# openevsetester.net
KiCad netlist of a schematic drawn in EAGLE
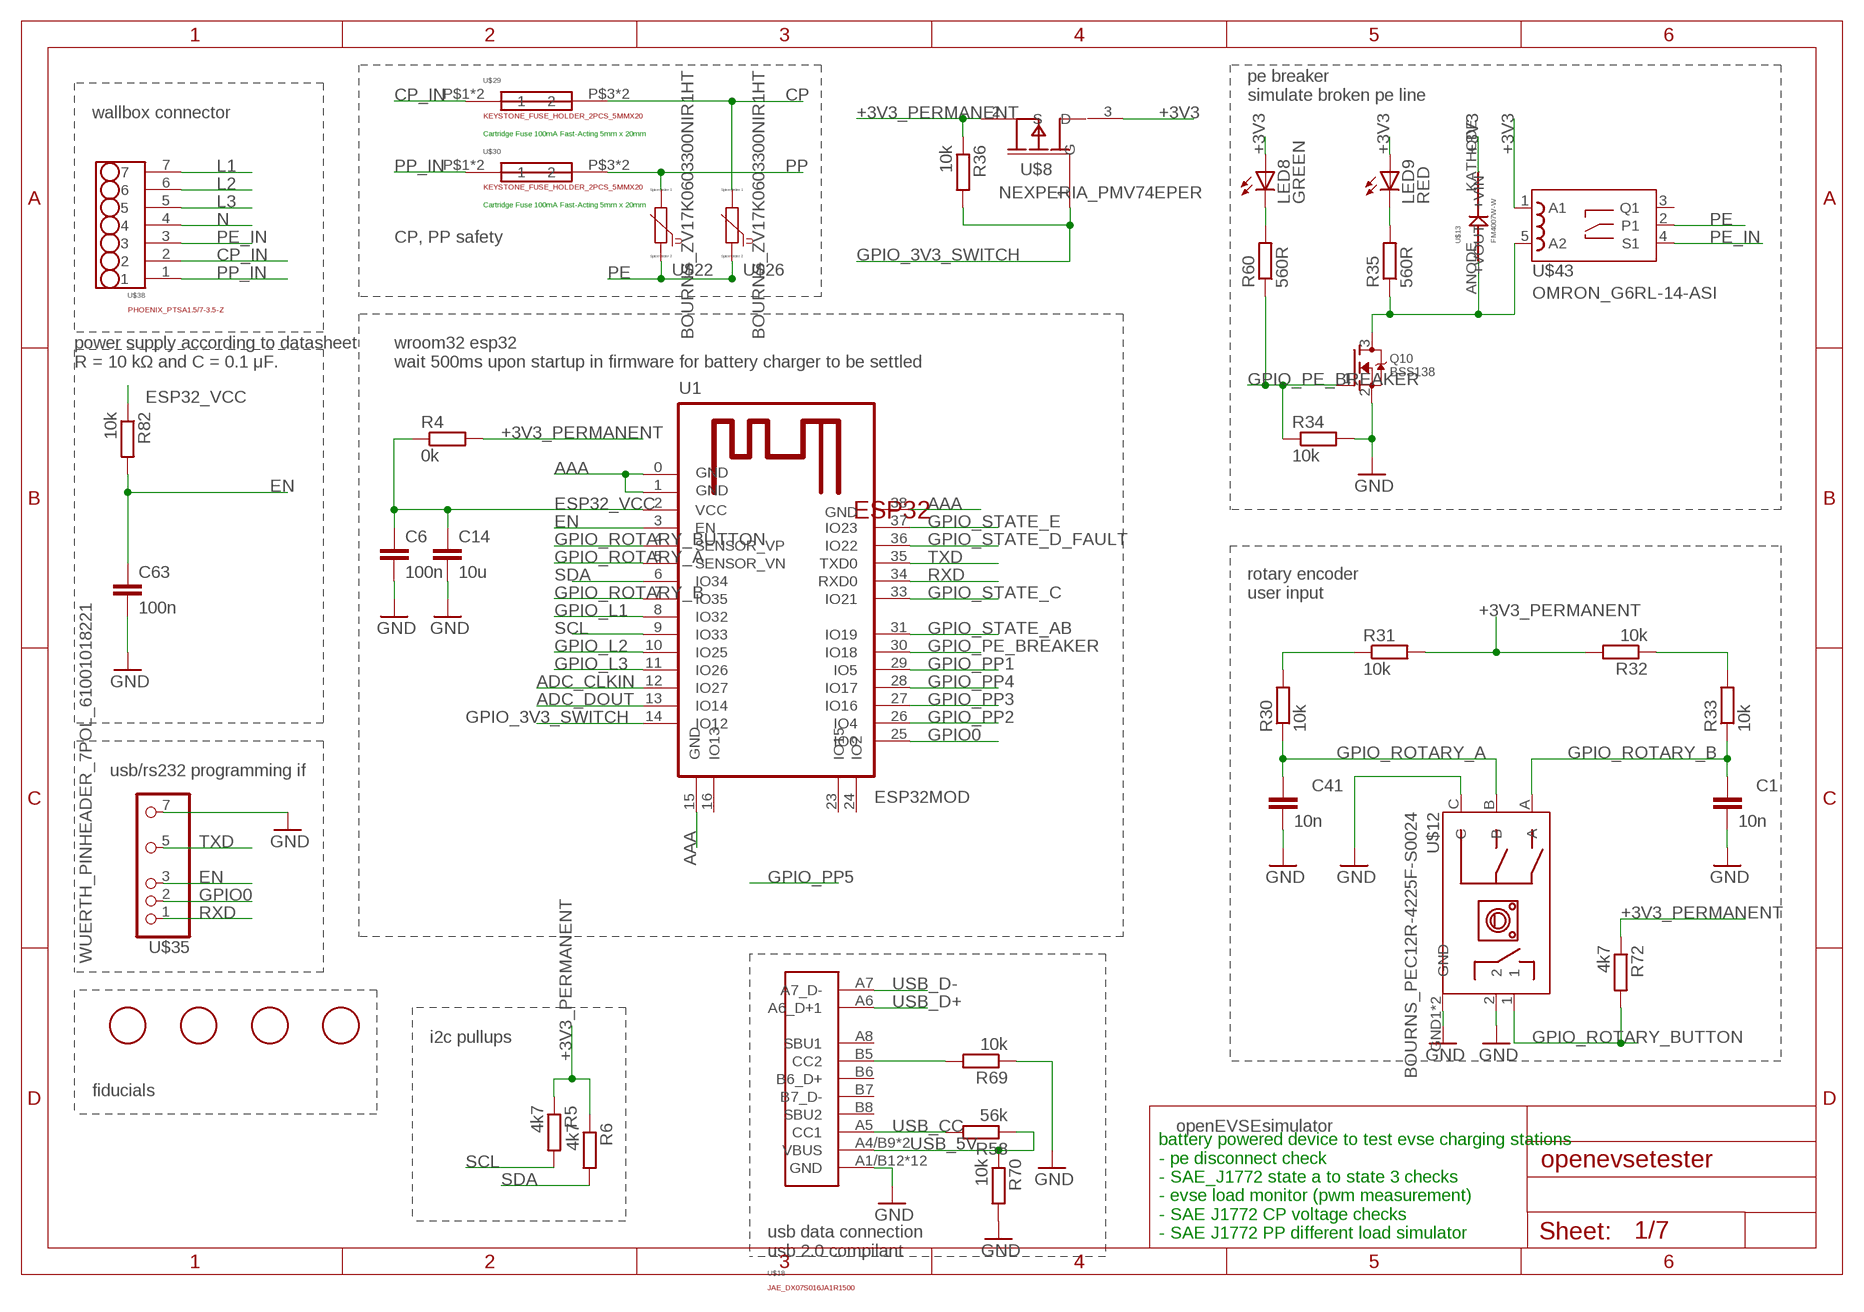
[diagram p0: schematic, sheet 1]
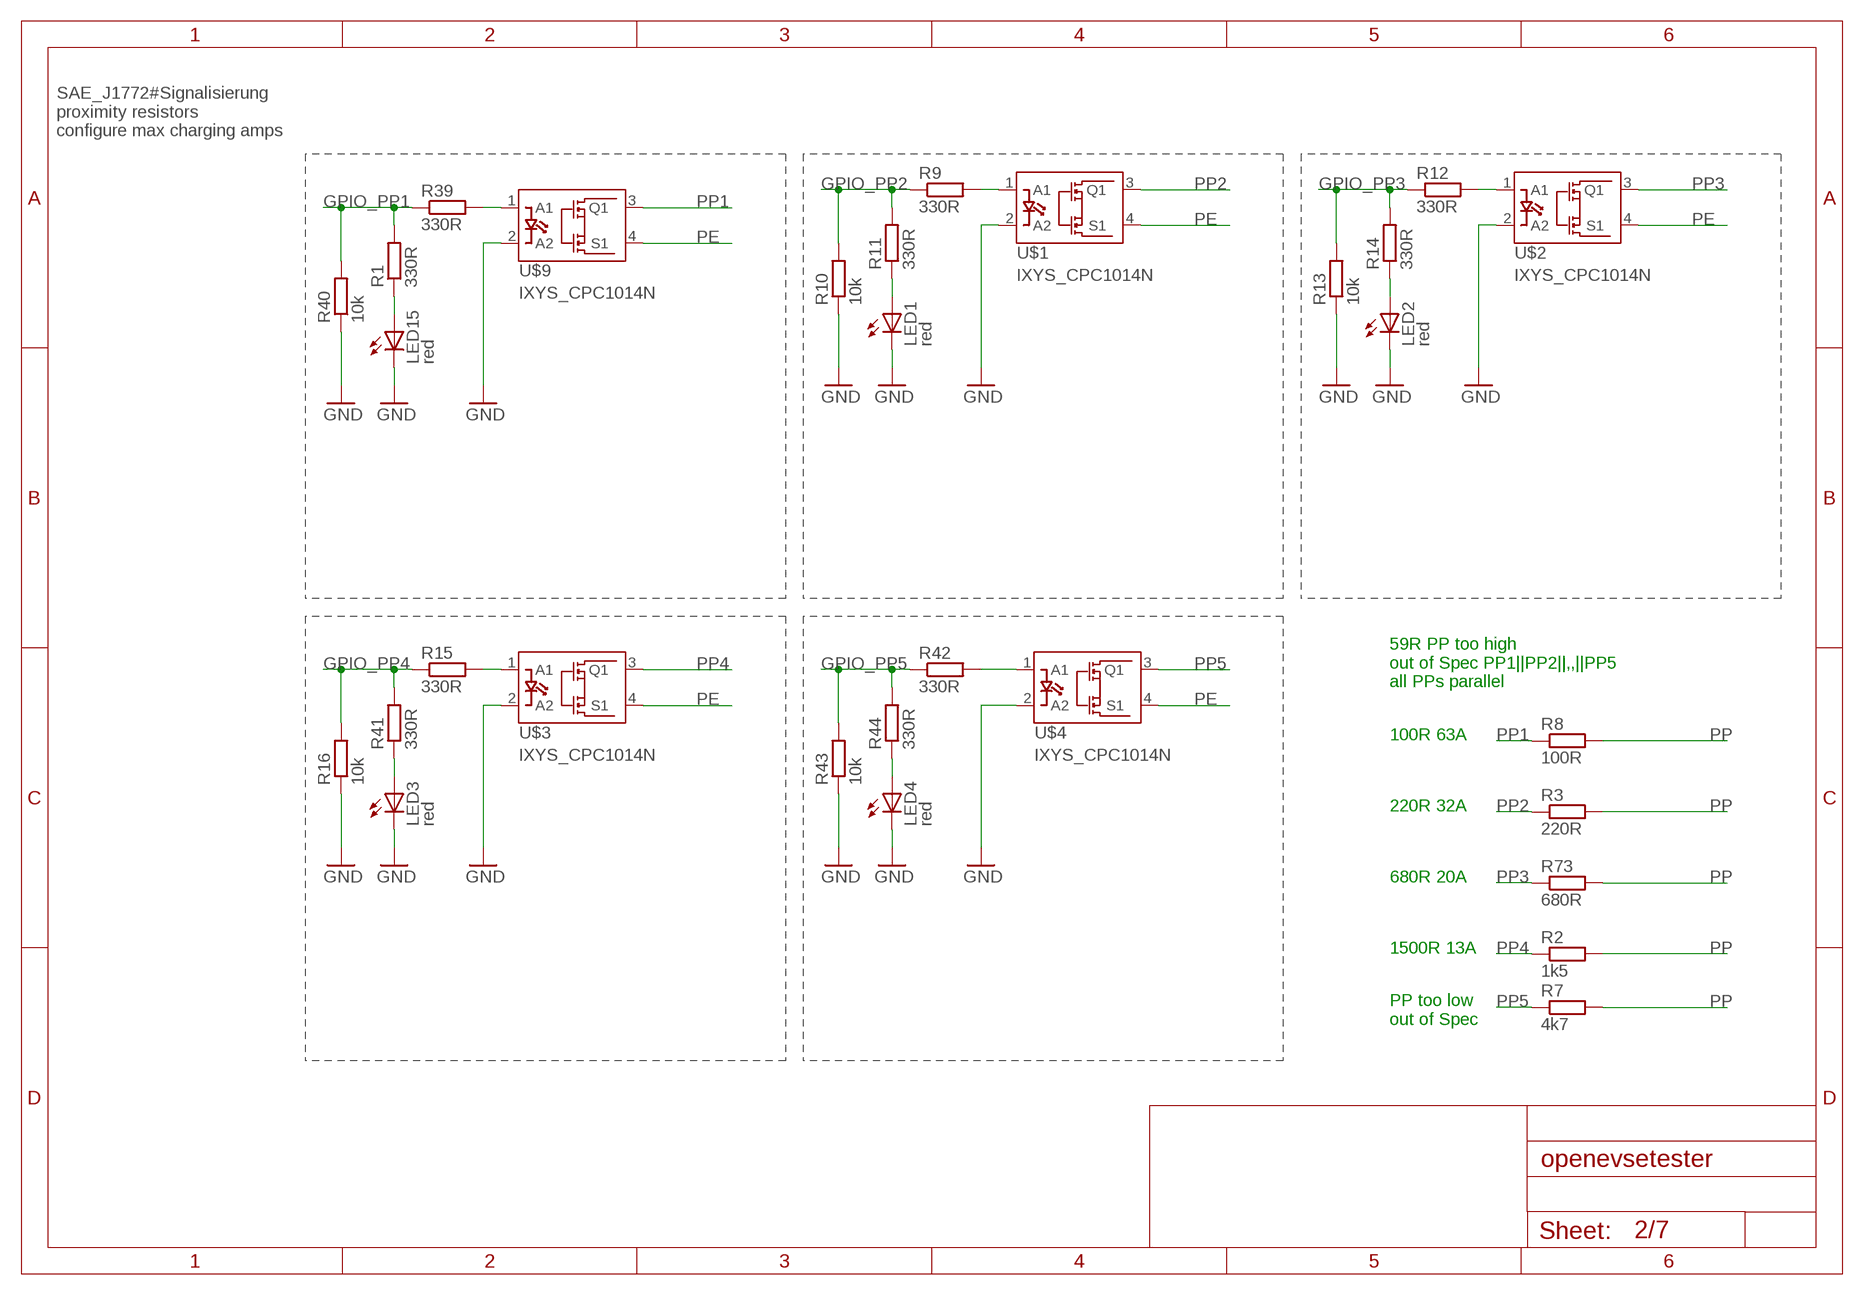
[diagram p1: schematic, sheet 2]
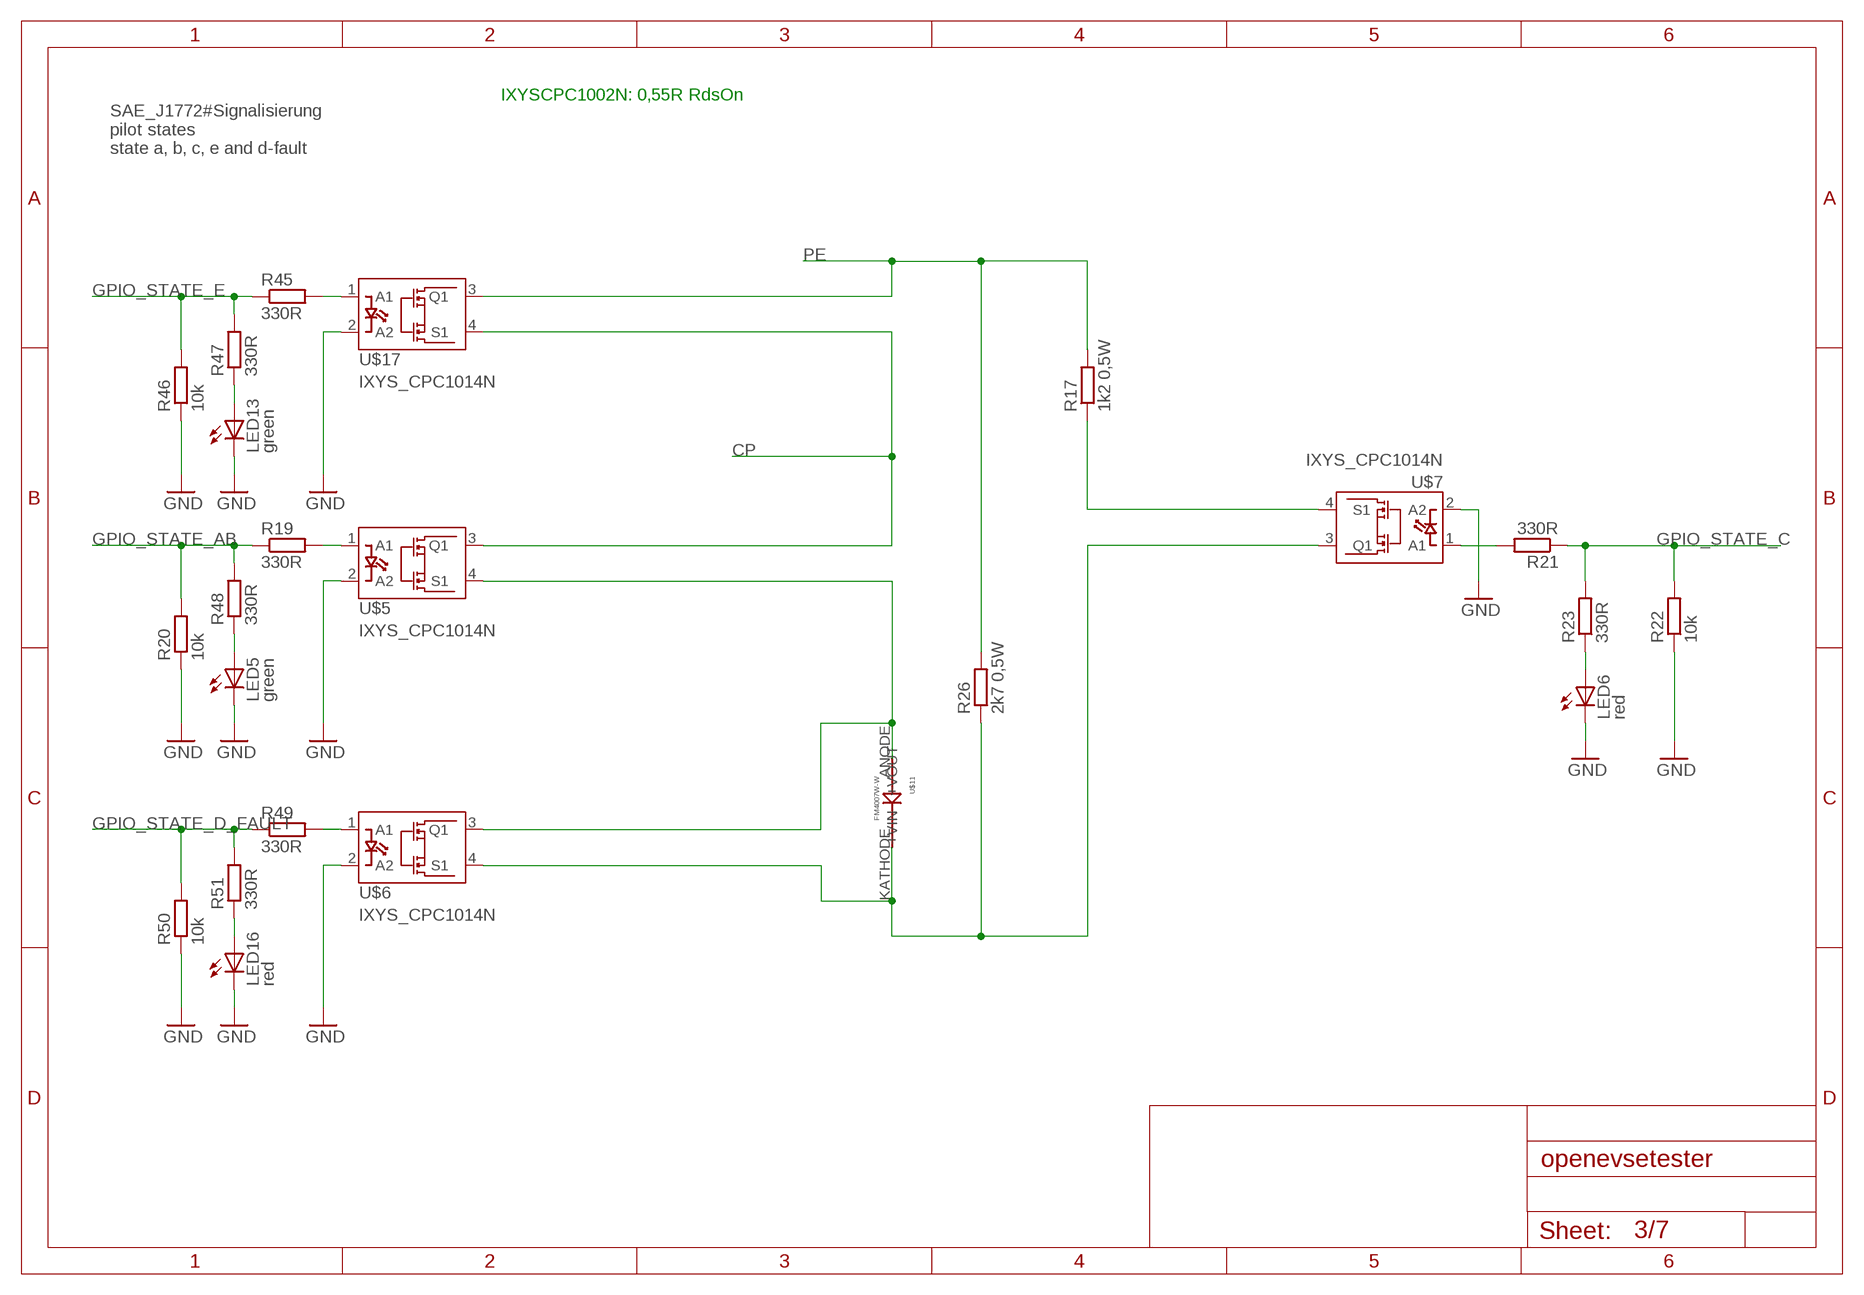
[diagram p2: schematic, sheet 3]
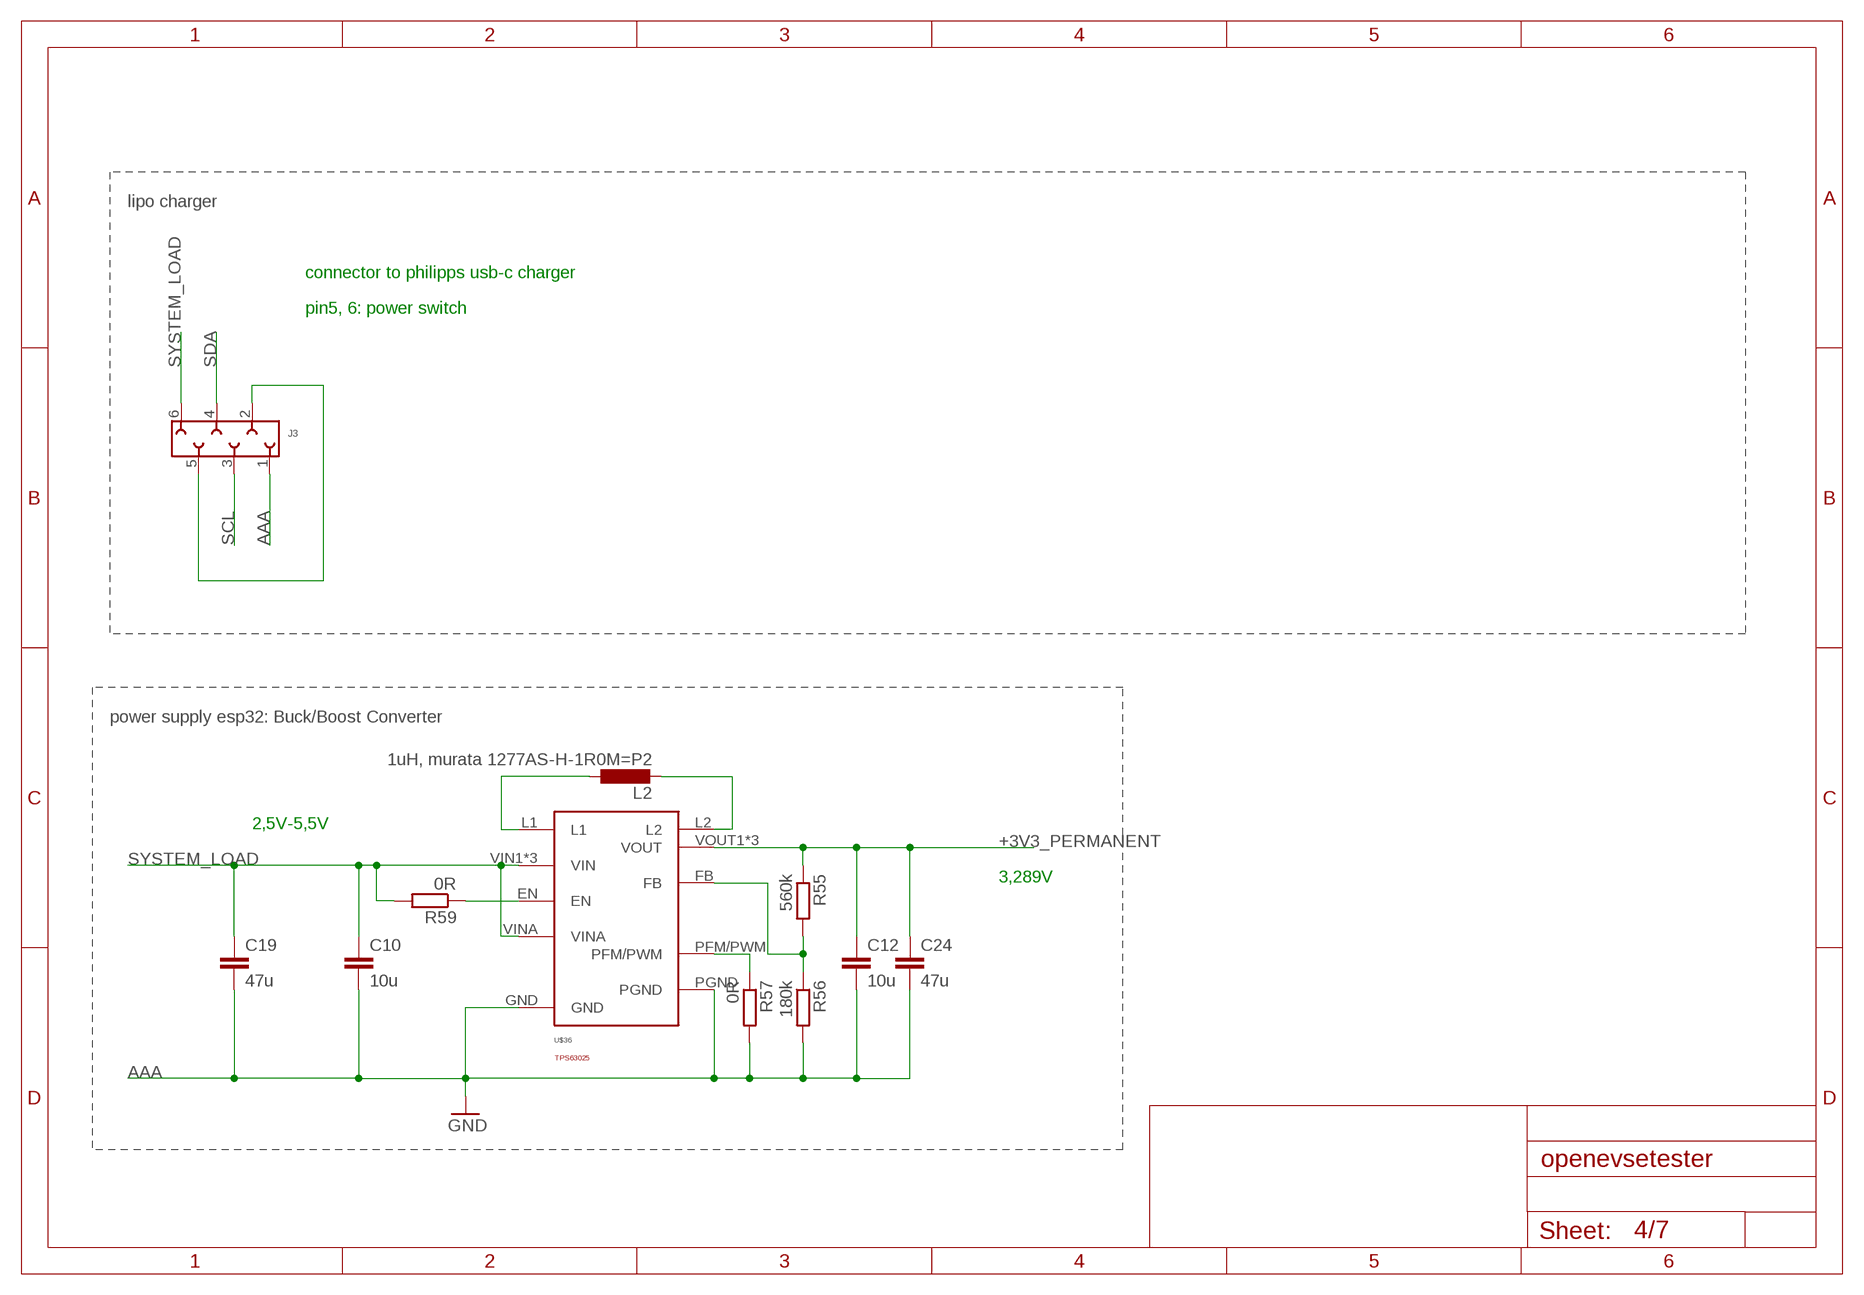
[diagram p3: schematic, sheet 4]
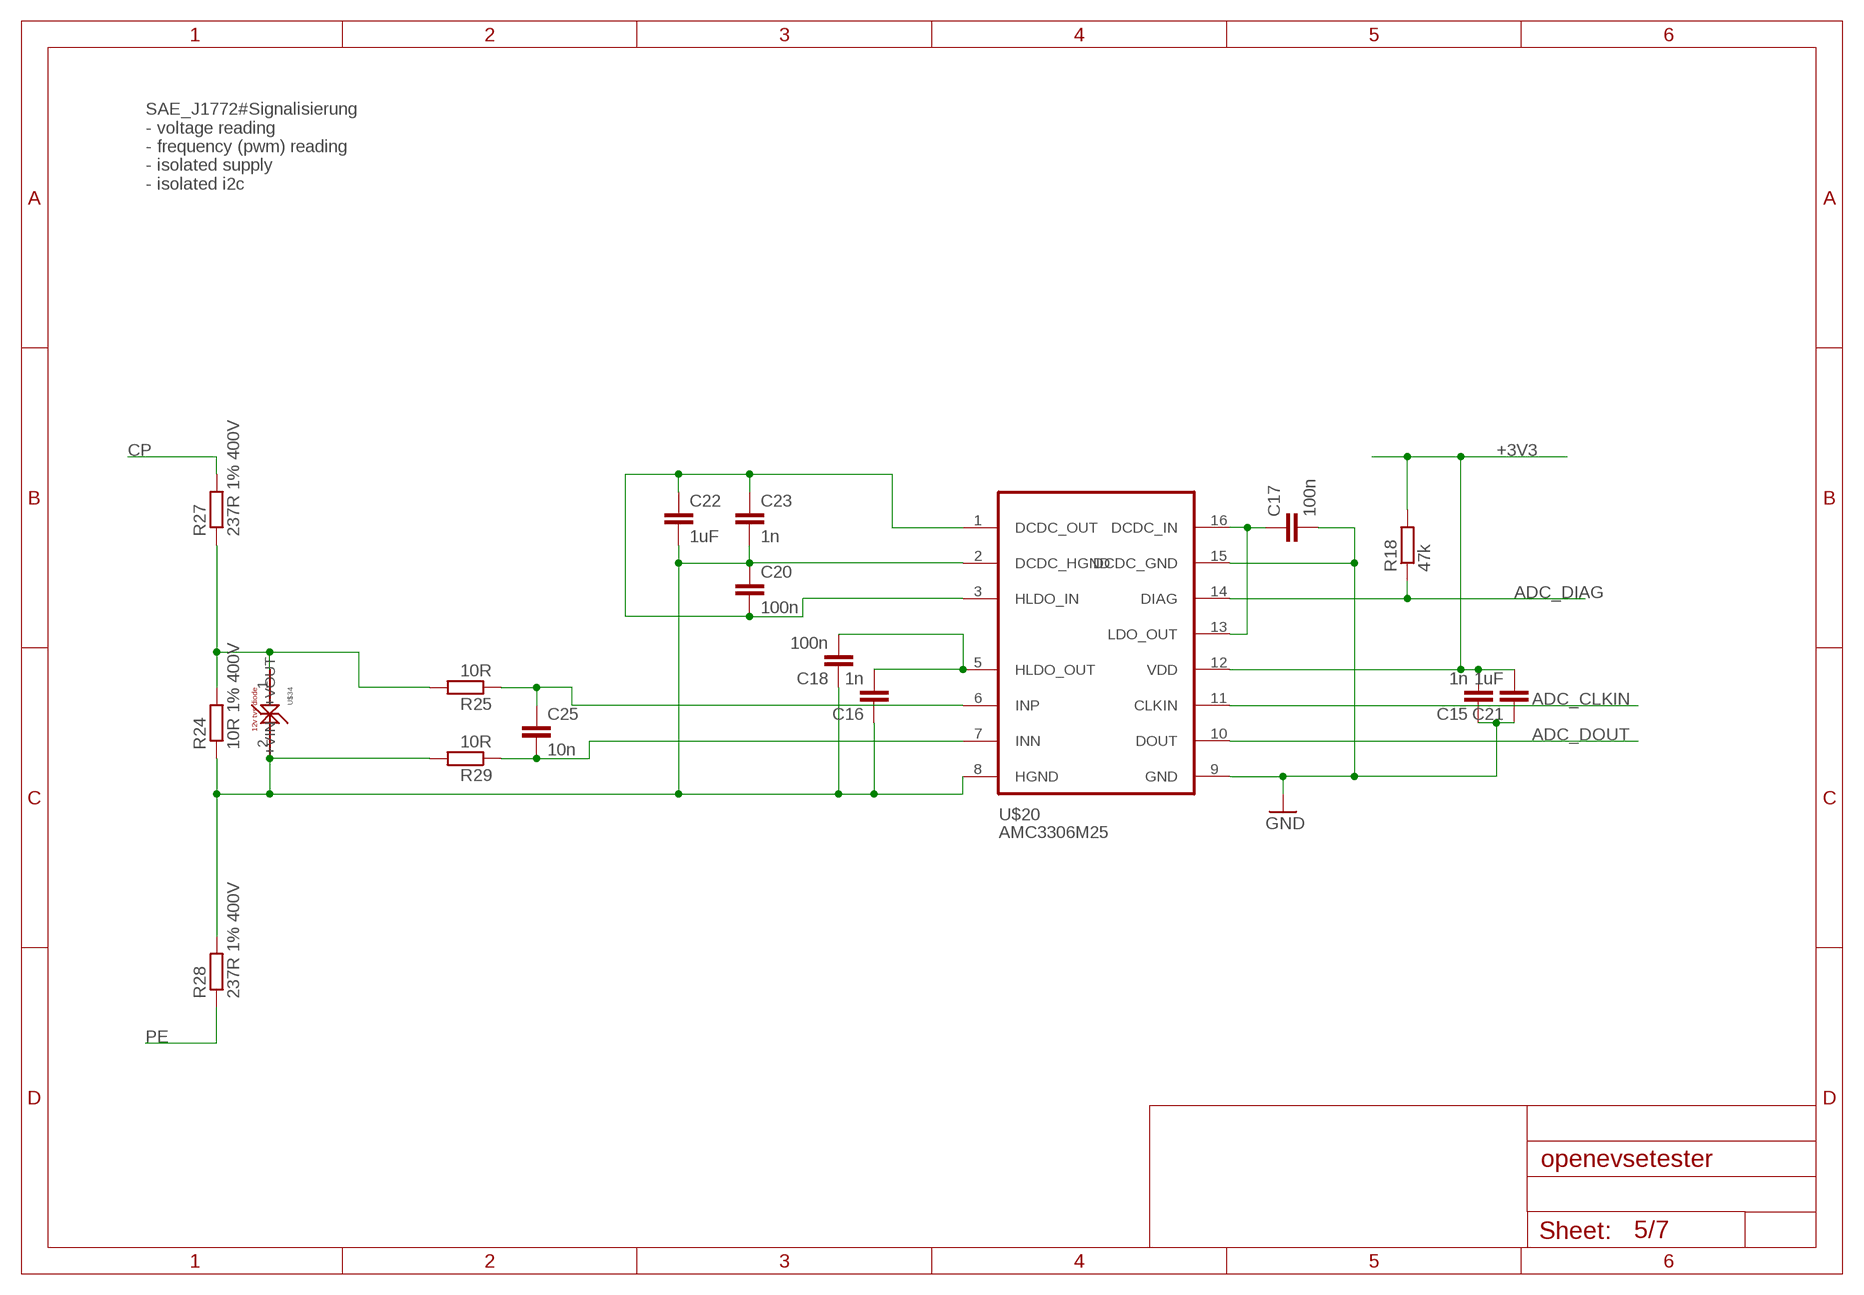
[diagram p4: schematic, sheet 5]
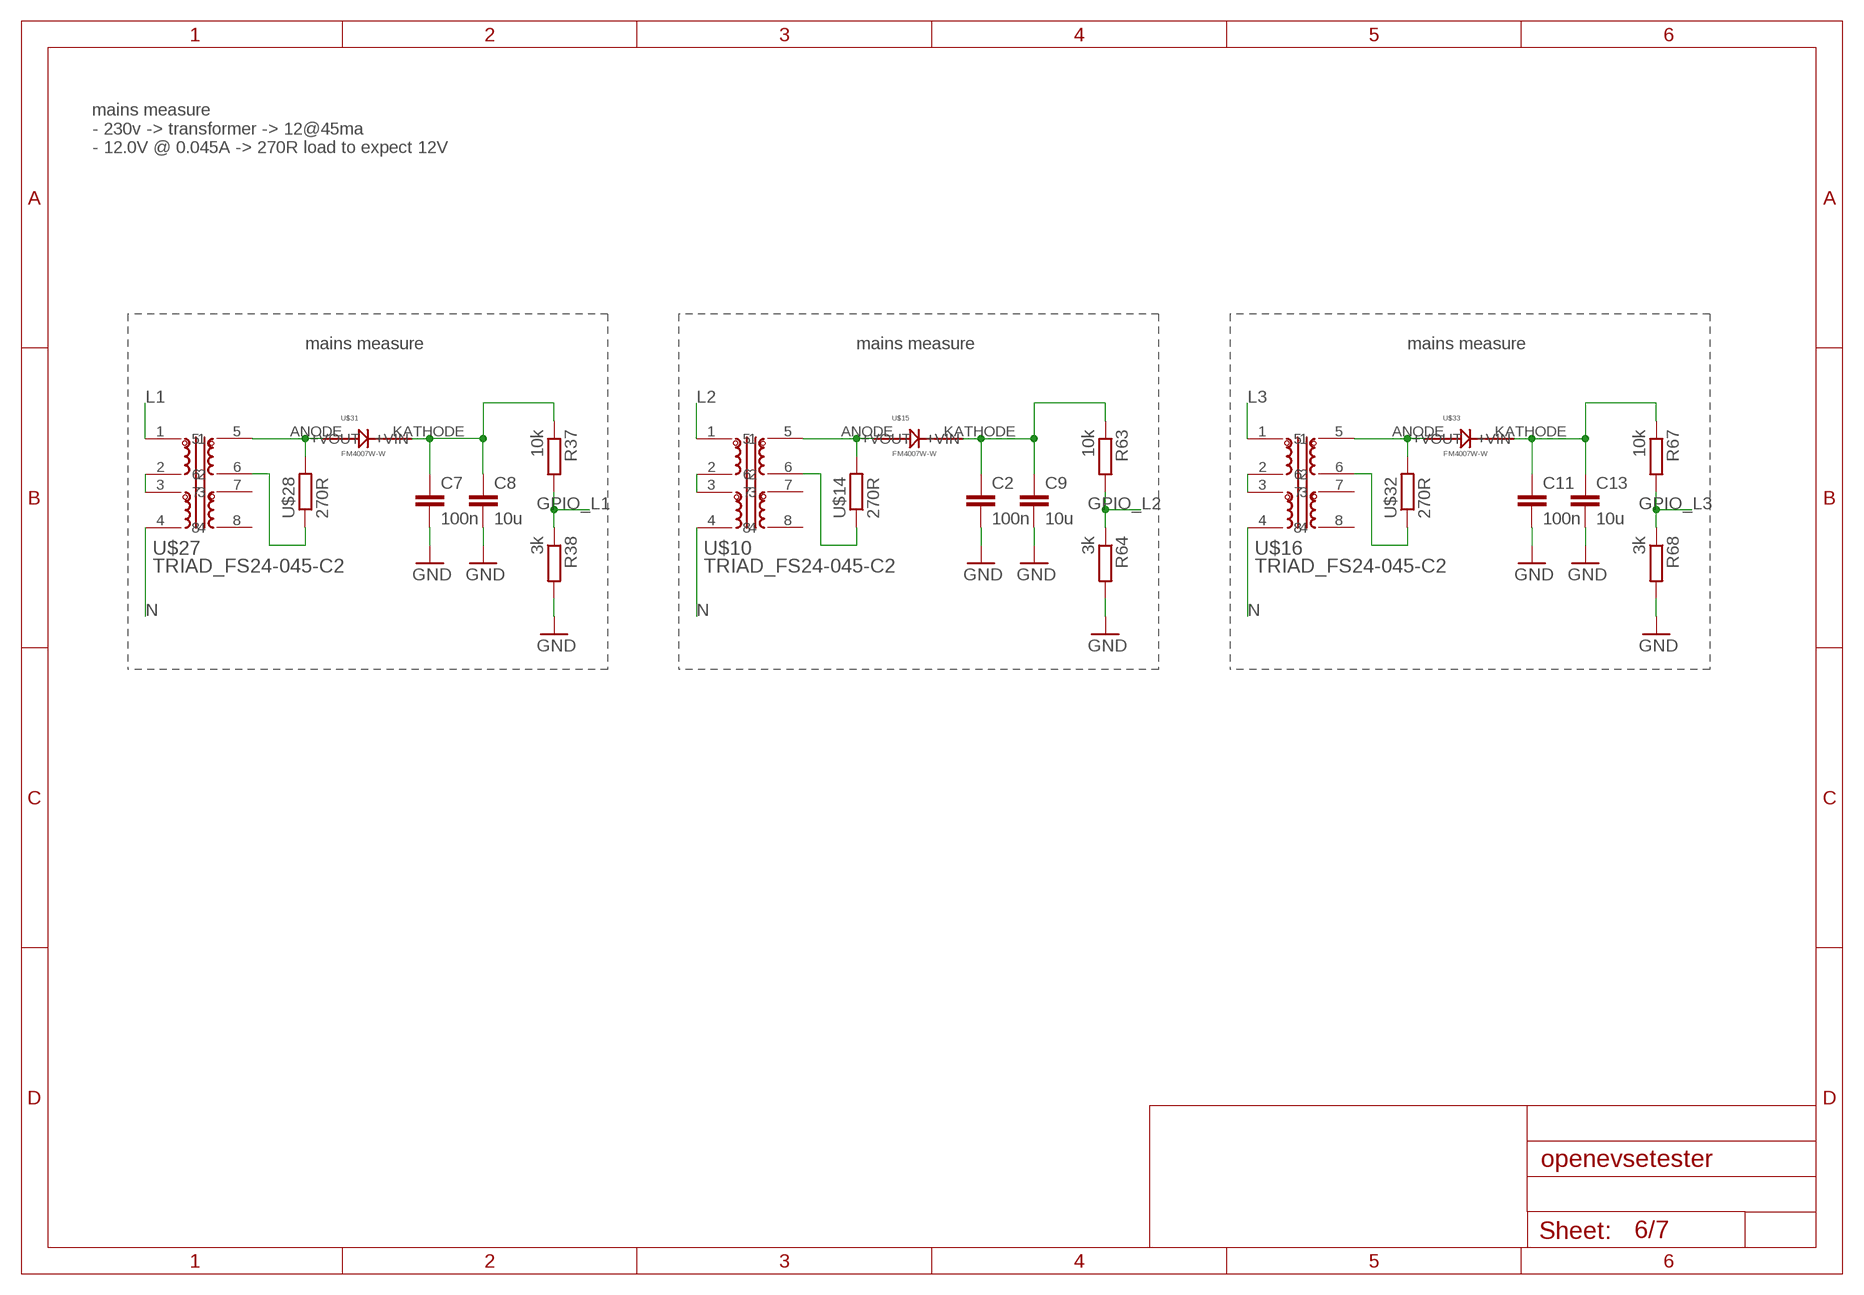
[diagram p5: schematic, sheet 6]
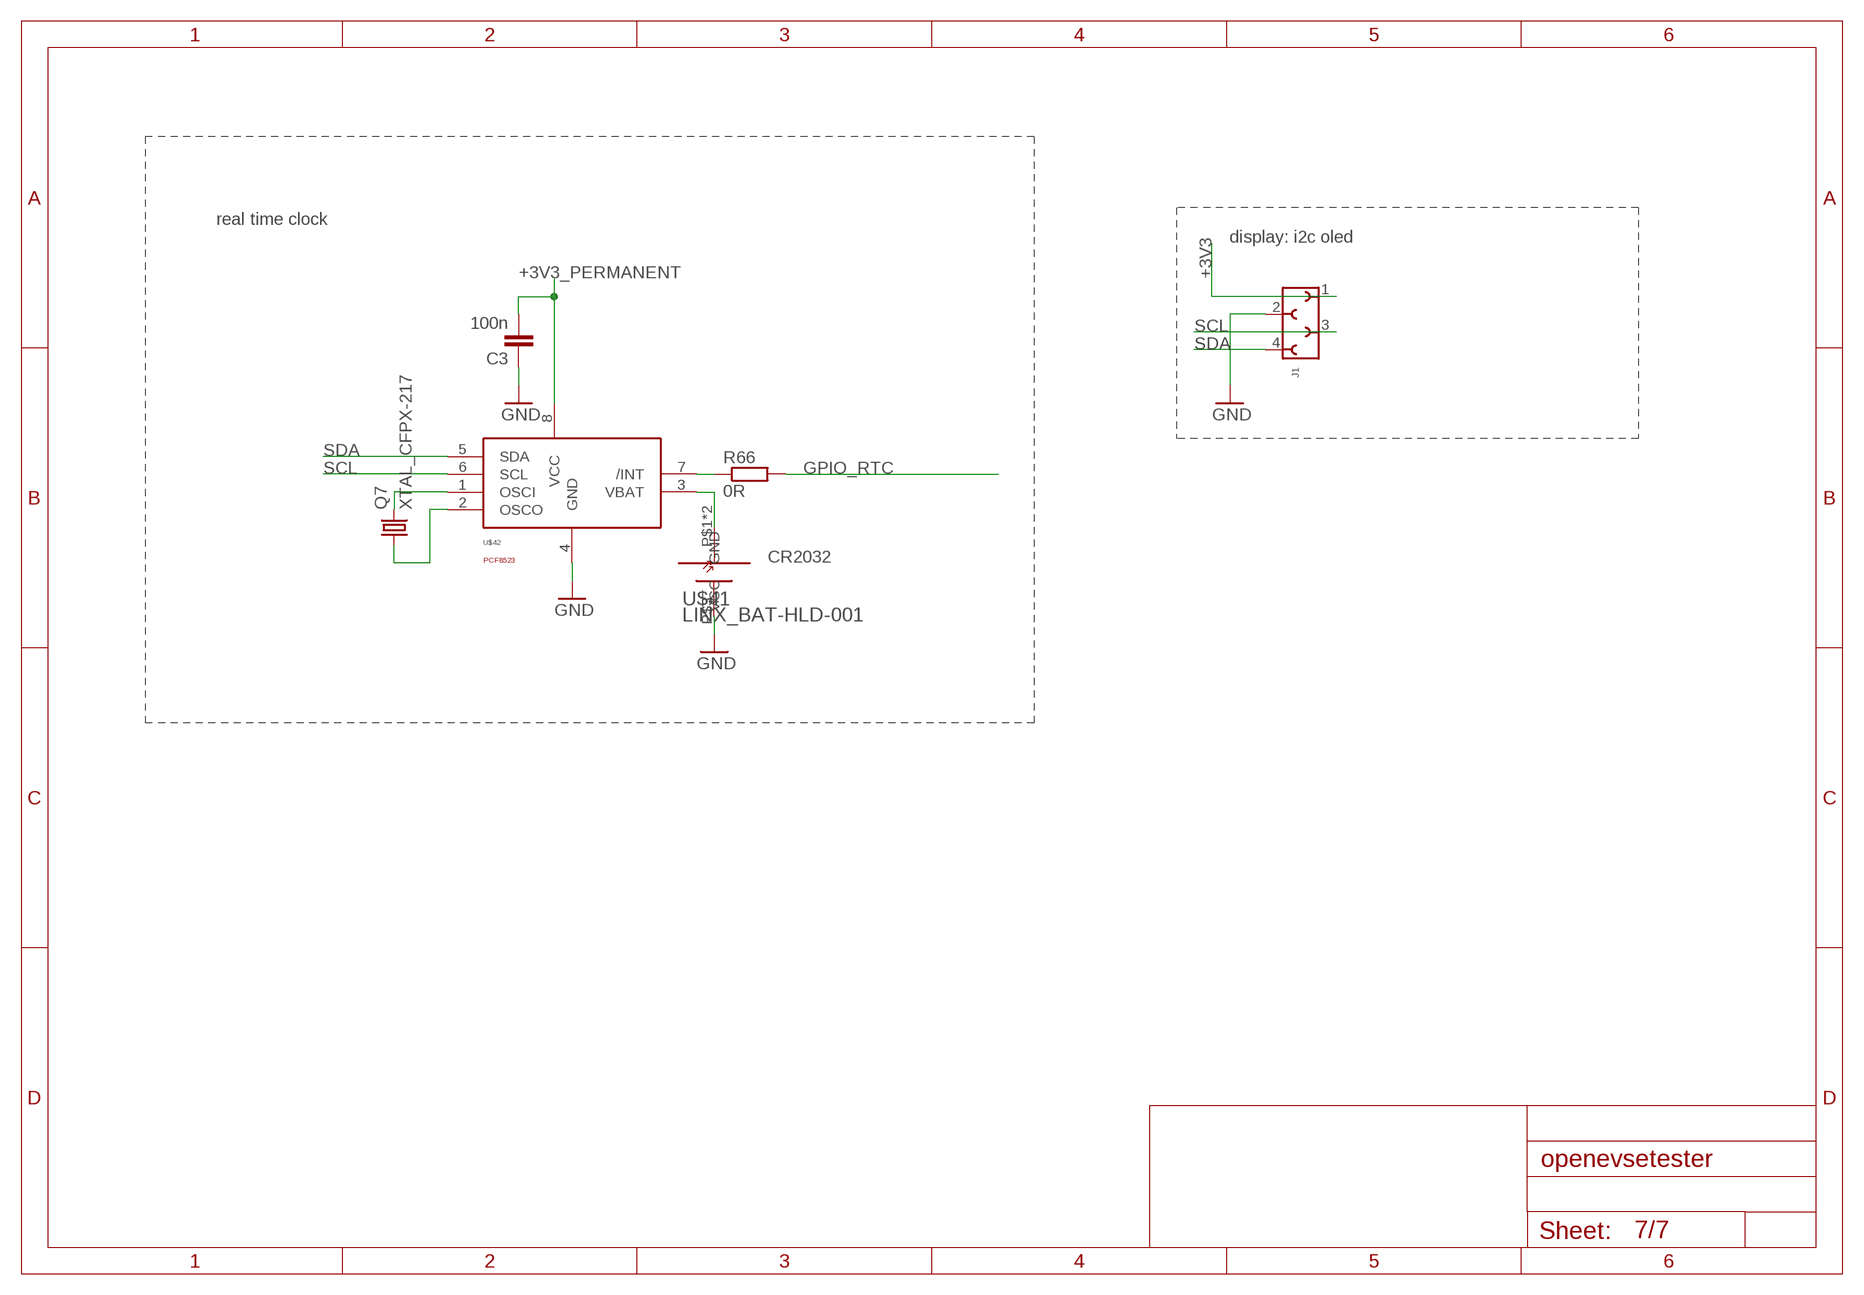
[diagram p6: schematic, sheet 7]

(export (version "E")
  (design (tool "Eeschema 10.0.6"))
  (components
    (comp (ref "LED1")
      (value "red")
      (footprint "eagle-import:SML0603")
      (libsource (lib "eagle-import") (part "LEDSML0603"))
    )
    (comp (ref "LED2")
      (value "red")
      (footprint "eagle-import:SML0603")
      (libsource (lib "eagle-import") (part "LEDSML0603"))
    )
    (comp (ref "LED3")
      (value "red")
      (footprint "eagle-import:SML0603")
      (libsource (lib "eagle-import") (part "LEDSML0603"))
    )
    (comp (ref "LED4")
      (value "red")
      (footprint "eagle-import:SML0603")
      (libsource (lib "eagle-import") (part "LEDSML0603"))
    )
    (comp (ref "LED15")
      (value "red")
      (footprint "eagle-import:SML0603")
      (libsource (lib "eagle-import") (part "LEDSML0603"))
    )
    (comp (ref "R1")
      (value "330R")
      (footprint "eagle-import:R0402")
      (libsource (lib "eagle-import") (part "R-EU_R0402"))
    )
    (comp (ref "R2")
      (value "1k5")
      (footprint "eagle-import:R1210")
      (libsource (lib "eagle-import") (part "resistor_348_R-EU_R1210"))
    )
    (comp (ref "R3")
      (value "220R")
      (footprint "eagle-import:R1210")
      (libsource (lib "eagle-import") (part "resistor_348_R-EU_R1210"))
    )
    (comp (ref "R7")
      (value "4k7")
      (footprint "eagle-import:R1210")
      (libsource (lib "eagle-import") (part "resistor_348_R-EU_R1210"))
    )
    (comp (ref "R8")
      (value "100R")
      (footprint "eagle-import:R1210")
      (libsource (lib "eagle-import") (part "resistor_348_R-EU_R1210"))
    )
    (comp (ref "R9")
      (value "330R")
      (footprint "eagle-import:R0402")
      (libsource (lib "eagle-import") (part "R-EU_R0402"))
    )
    (comp (ref "R10")
      (value "10k")
      (footprint "eagle-import:R0402")
      (libsource (lib "eagle-import") (part "R-EU_R0402"))
    )
    (comp (ref "R11")
      (value "330R")
      (footprint "eagle-import:R0402")
      (libsource (lib "eagle-import") (part "R-EU_R0402"))
    )
    (comp (ref "R12")
      (value "330R")
      (footprint "eagle-import:R0402")
      (libsource (lib "eagle-import") (part "R-EU_R0402"))
    )
    (comp (ref "R13")
      (value "10k")
      (footprint "eagle-import:R0402")
      (libsource (lib "eagle-import") (part "R-EU_R0402"))
    )
    (comp (ref "R14")
      (value "330R")
      (footprint "eagle-import:R0402")
      (libsource (lib "eagle-import") (part "R-EU_R0402"))
    )
    (comp (ref "R15")
      (value "330R")
      (footprint "eagle-import:R0402")
      (libsource (lib "eagle-import") (part "R-EU_R0402"))
    )
    (comp (ref "R16")
      (value "10k")
      (footprint "eagle-import:R0402")
      (libsource (lib "eagle-import") (part "R-EU_R0402"))
    )
    (comp (ref "R39")
      (value "330R")
      (footprint "eagle-import:R0402")
      (libsource (lib "eagle-import") (part "R-EU_R0402"))
    )
    (comp (ref "R40")
      (value "10k")
      (footprint "eagle-import:R0402")
      (libsource (lib "eagle-import") (part "R-EU_R0402"))
    )
    (comp (ref "R41")
      (value "330R")
      (footprint "eagle-import:R0402")
      (libsource (lib "eagle-import") (part "R-EU_R0402"))
    )
    (comp (ref "R42")
      (value "330R")
      (footprint "eagle-import:R0402")
      (libsource (lib "eagle-import") (part "R-EU_R0402"))
    )
    (comp (ref "R43")
      (value "10k")
      (footprint "eagle-import:R0402")
      (libsource (lib "eagle-import") (part "R-EU_R0402"))
    )
    (comp (ref "R44")
      (value "330R")
      (footprint "eagle-import:R0402")
      (libsource (lib "eagle-import") (part "R-EU_R0402"))
    )
    (comp (ref "R73")
      (value "680R")
      (footprint "eagle-import:R1210")
      (libsource (lib "eagle-import") (part "resistor_348_R-EU_R1210"))
    )
    (comp (ref "U$1")
      (value "IXYS_CPC1014N")
      (footprint "eagle-import:SOIC-4")
      (libsource (lib "eagle-import") (part "IXYS_CPC1014N"))
    )
    (comp (ref "U$2")
      (value "IXYS_CPC1014N")
      (footprint "eagle-import:SOIC-4")
      (libsource (lib "eagle-import") (part "IXYS_CPC1014N"))
    )
    (comp (ref "U$3")
      (value "IXYS_CPC1014N")
      (footprint "eagle-import:SOIC-4")
      (libsource (lib "eagle-import") (part "IXYS_CPC1014N"))
    )
    (comp (ref "U$4")
      (value "IXYS_CPC1014N")
      (footprint "eagle-import:SOIC-4")
      (libsource (lib "eagle-import") (part "IXYS_CPC1014N"))
    )
    (comp (ref "U$9")
      (value "IXYS_CPC1014N")
      (footprint "eagle-import:SOIC-4")
      (libsource (lib "eagle-import") (part "IXYS_CPC1014N"))
    )
    (comp (ref "C10")
      (value "10u")
      (footprint "eagle-import:C0805")
      (libsource (lib "eagle-import") (part "rcl_334_C-EUC0805"))
    )
    (comp (ref "C12")
      (value "10u")
      (footprint "eagle-import:C0805")
      (libsource (lib "eagle-import") (part "rcl_334_C-EUC0805"))
    )
    (comp (ref "C19")
      (value "47u")
      (footprint "eagle-import:C1206")
      (libsource (lib "eagle-import") (part "rcl_334_C-EUC1206"))
    )
    (comp (ref "C24")
      (value "47u")
      (footprint "eagle-import:C0805")
      (libsource (lib "eagle-import") (part "rcl_334_C-EUC0805"))
    )
    (comp (ref "J3")
      (value "6100XX11921_61000611921")
      (footprint "eagle-import:61000611921")
      (libsource (lib "eagle-import") (part "6100XX11921_61000611921"))
    )
    (comp (ref "L2")
      (value "1uH, murata 1277AS-H-1R0M=P2")
      (footprint "eagle-import:L3225M")
      (libsource (lib "eagle-import") (part "L-EUL3225M"))
    )
    (comp (ref "R55")
      (value "560k")
      (footprint "eagle-import:R0402")
      (libsource (lib "eagle-import") (part "R-EU_R0402"))
    )
    (comp (ref "R56")
      (value "180k")
      (footprint "eagle-import:R0402")
      (libsource (lib "eagle-import") (part "R-EU_R0402"))
    )
    (comp (ref "R57")
      (value "0R")
      (footprint "eagle-import:R0402")
      (libsource (lib "eagle-import") (part "R-EU_R0402"))
    )
    (comp (ref "R59")
      (value "0R")
      (footprint "eagle-import:R0402")
      (libsource (lib "eagle-import") (part "R-EU_R0402"))
    )
    (comp (ref "U$36")
      (value "TPS63025")
      (footprint "eagle-import:VQFN14")
      (libsource (lib "eagle-import") (part "TPS63025"))
    )
    (comp (ref "LED5")
      (value "green")
      (footprint "eagle-import:SML0603")
      (libsource (lib "eagle-import") (part "LEDSML0603"))
    )
    (comp (ref "LED6")
      (value "red")
      (footprint "eagle-import:SML0603")
      (libsource (lib "eagle-import") (part "LEDSML0603"))
    )
    (comp (ref "LED13")
      (value "green")
      (footprint "eagle-import:SML0603")
      (libsource (lib "eagle-import") (part "LEDSML0603"))
    )
    (comp (ref "LED16")
      (value "red")
      (footprint "eagle-import:SML0603")
      (libsource (lib "eagle-import") (part "LEDSML0603"))
    )
    (comp (ref "R17")
      (value "1k2 0,5W")
      (footprint "eagle-import:R0805")
      (libsource (lib "eagle-import") (part "resistor_348_R-EU_R0805"))
    )
    (comp (ref "R19")
      (value "330R")
      (footprint "eagle-import:R0402")
      (libsource (lib "eagle-import") (part "R-EU_R0402"))
    )
    (comp (ref "R20")
      (value "10k")
      (footprint "eagle-import:R0402")
      (libsource (lib "eagle-import") (part "R-EU_R0402"))
    )
    (comp (ref "R21")
      (value "330R")
      (footprint "eagle-import:R0402")
      (libsource (lib "eagle-import") (part "R-EU_R0402"))
    )
    (comp (ref "R22")
      (value "10k")
      (footprint "eagle-import:R0402")
      (libsource (lib "eagle-import") (part "R-EU_R0402"))
    )
    (comp (ref "R23")
      (value "330R")
      (footprint "eagle-import:R0402")
      (libsource (lib "eagle-import") (part "R-EU_R0402"))
    )
    (comp (ref "R26")
      (value "2k7 0,5W")
      (footprint "eagle-import:R0805")
      (libsource (lib "eagle-import") (part "resistor_348_R-EU_R0805"))
    )
    (comp (ref "R45")
      (value "330R")
      (footprint "eagle-import:R0402")
      (libsource (lib "eagle-import") (part "R-EU_R0402"))
    )
    (comp (ref "R46")
      (value "10k")
      (footprint "eagle-import:R0402")
      (libsource (lib "eagle-import") (part "R-EU_R0402"))
    )
    (comp (ref "R47")
      (value "330R")
      (footprint "eagle-import:R0402")
      (libsource (lib "eagle-import") (part "R-EU_R0402"))
    )
    (comp (ref "R48")
      (value "330R")
      (footprint "eagle-import:R0402")
      (libsource (lib "eagle-import") (part "R-EU_R0402"))
    )
    (comp (ref "R49")
      (value "330R")
      (footprint "eagle-import:R0402")
      (libsource (lib "eagle-import") (part "R-EU_R0402"))
    )
    (comp (ref "R50")
      (value "10k")
      (footprint "eagle-import:R0402")
      (libsource (lib "eagle-import") (part "R-EU_R0402"))
    )
    (comp (ref "R51")
      (value "330R")
      (footprint "eagle-import:R0402")
      (libsource (lib "eagle-import") (part "R-EU_R0402"))
    )
    (comp (ref "U$5")
      (value "IXYS_CPC1014N")
      (footprint "eagle-import:SOIC-4")
      (libsource (lib "eagle-import") (part "IXYS_CPC1014N"))
    )
    (comp (ref "U$6")
      (value "IXYS_CPC1014N")
      (footprint "eagle-import:SOIC-4")
      (libsource (lib "eagle-import") (part "IXYS_CPC1014N"))
    )
    (comp (ref "U$7")
      (value "IXYS_CPC1014N")
      (footprint "eagle-import:SOIC-4")
      (libsource (lib "eagle-import") (part "IXYS_CPC1014N"))
    )
    (comp (ref "U$11")
      (value "FM4007W-W")
      (footprint "eagle-import:SMX")
      (libsource (lib "eagle-import") (part "FM4007W-W"))
    )
    (comp (ref "U$17")
      (value "IXYS_CPC1014N")
      (footprint "eagle-import:SOIC-4")
      (libsource (lib "eagle-import") (part "IXYS_CPC1014N"))
    )
    (comp (ref "C15")
      (value "1n")
      (footprint "eagle-import:C1206")
      (libsource (lib "eagle-import") (part "resistor_348_C-EUC1206"))
    )
    (comp (ref "C16")
      (value "1n")
      (footprint "eagle-import:C1206")
      (libsource (lib "eagle-import") (part "resistor_348_C-EUC1206"))
    )
    (comp (ref "C17")
      (value "100n")
      (footprint "eagle-import:C0603")
      (libsource (lib "eagle-import") (part "resistor_348_C-EUC0603"))
    )
    (comp (ref "C18")
      (value "100n")
      (footprint "eagle-import:C1206")
      (libsource (lib "eagle-import") (part "resistor_348_C-EUC1206"))
    )
    (comp (ref "C20")
      (value "100n")
      (footprint "eagle-import:C0603")
      (libsource (lib "eagle-import") (part "resistor_348_C-EUC0603"))
    )
    (comp (ref "C21")
      (value "1uF")
      (footprint "eagle-import:C1206")
      (libsource (lib "eagle-import") (part "resistor_348_C-EUC1206"))
    )
    (comp (ref "C22")
      (value "1uF")
      (footprint "eagle-import:C0603")
      (libsource (lib "eagle-import") (part "resistor_348_C-EUC0603"))
    )
    (comp (ref "C23")
      (value "1n")
      (footprint "eagle-import:C0603")
      (libsource (lib "eagle-import") (part "resistor_348_C-EUC0603"))
    )
    (comp (ref "C25")
      (value "10n")
      (footprint "eagle-import:C0603")
      (libsource (lib "eagle-import") (part "resistor_348_C-EUC0603"))
    )
    (comp (ref "R18")
      (value "47k")
      (footprint "eagle-import:R0402")
      (libsource (lib "eagle-import") (part "R-EU_R0402"))
    )
    (comp (ref "R24")
      (value "10R 1% 400V")
      (footprint "eagle-import:R2512")
      (libsource (lib "eagle-import") (part "resistor_348_R-EU_R2512"))
    )
    (comp (ref "R25")
      (value "10R")
      (footprint "eagle-import:R2512")
      (libsource (lib "eagle-import") (part "resistor_348_R-EU_R2512"))
    )
    (comp (ref "R27")
      (value "237R 1% 400V")
      (footprint "eagle-import:R2010")
      (libsource (lib "eagle-import") (part "resistor_348_R-EU_R2010"))
    )
    (comp (ref "R28")
      (value "237R 1% 400V")
      (footprint "eagle-import:R2010")
      (libsource (lib "eagle-import") (part "resistor_348_R-EU_R2010"))
    )
    (comp (ref "R29")
      (value "10R")
      (footprint "eagle-import:R2512")
      (libsource (lib "eagle-import") (part "resistor_348_R-EU_R2512"))
    )
    (comp (ref "U$20")
      (value "AMC3306M25")
      (footprint "eagle-import:SOIC-16")
      (libsource (lib "eagle-import") (part "AMC3306M25"))
    )
    (comp (ref "U$34")
      (value "12v tvs diode")
      (footprint "eagle-import:0402")
      (libsource (lib "eagle-import") (part "LXESXXA"))
    )
    (comp (ref "C2")
      (value "100n")
      (footprint "eagle-import:C0402")
      (libsource (lib "eagle-import") (part "C-EUC0402"))
    )
    (comp (ref "C7")
      (value "100n")
      (footprint "eagle-import:C0402")
      (libsource (lib "eagle-import") (part "C-EUC0402"))
    )
    (comp (ref "C8")
      (value "10u")
      (footprint "eagle-import:C0805")
      (libsource (lib "eagle-import") (part "rcl_334_C-EUC0805"))
    )
    (comp (ref "C9")
      (value "10u")
      (footprint "eagle-import:C0805")
      (libsource (lib "eagle-import") (part "rcl_334_C-EUC0805"))
    )
    (comp (ref "C11")
      (value "100n")
      (footprint "eagle-import:C0402")
      (libsource (lib "eagle-import") (part "C-EUC0402"))
    )
    (comp (ref "C13")
      (value "10u")
      (footprint "eagle-import:C0805")
      (libsource (lib "eagle-import") (part "rcl_334_C-EUC0805"))
    )
    (comp (ref "R37")
      (value "10k")
      (footprint "eagle-import:R0402")
      (libsource (lib "eagle-import") (part "R-EU_R0402"))
    )
    (comp (ref "R38")
      (value "3k")
      (footprint "eagle-import:R0402")
      (libsource (lib "eagle-import") (part "R-EU_R0402"))
    )
    (comp (ref "R63")
      (value "10k")
      (footprint "eagle-import:R0402")
      (libsource (lib "eagle-import") (part "R-EU_R0402"))
    )
    (comp (ref "R64")
      (value "3k")
      (footprint "eagle-import:R0402")
      (libsource (lib "eagle-import") (part "R-EU_R0402"))
    )
    (comp (ref "R67")
      (value "10k")
      (footprint "eagle-import:R0402")
      (libsource (lib "eagle-import") (part "R-EU_R0402"))
    )
    (comp (ref "R68")
      (value "3k")
      (footprint "eagle-import:R0402")
      (libsource (lib "eagle-import") (part "R-EU_R0402"))
    )
    (comp (ref "U$10")
      (value "TRIAD_FS24-045-C2")
      (footprint "eagle-import:TRIAD_FS24-045-C2")
      (libsource (lib "eagle-import") (part "TRIAD_FS24-045-C2"))
    )
    (comp (ref "U$14")
      (value "270R")
      (footprint "eagle-import:2512")
      (libsource (lib "eagle-import") (part "R2512"))
    )
    (comp (ref "U$15")
      (value "FM4007W-W")
      (footprint "eagle-import:SMX")
      (libsource (lib "eagle-import") (part "FM4007W-W"))
    )
    (comp (ref "U$16")
      (value "TRIAD_FS24-045-C2")
      (footprint "eagle-import:TRIAD_FS24-045-C2")
      (libsource (lib "eagle-import") (part "TRIAD_FS24-045-C2"))
    )
    (comp (ref "U$27")
      (value "TRIAD_FS24-045-C2")
      (footprint "eagle-import:TRIAD_FS24-045-C2")
      (libsource (lib "eagle-import") (part "TRIAD_FS24-045-C2"))
    )
    (comp (ref "U$28")
      (value "270R")
      (footprint "eagle-import:2512")
      (libsource (lib "eagle-import") (part "R2512"))
    )
    (comp (ref "U$31")
      (value "FM4007W-W")
      (footprint "eagle-import:SMX")
      (libsource (lib "eagle-import") (part "FM4007W-W"))
    )
    (comp (ref "U$32")
      (value "270R")
      (footprint "eagle-import:2512")
      (libsource (lib "eagle-import") (part "R2512"))
    )
    (comp (ref "U$33")
      (value "FM4007W-W")
      (footprint "eagle-import:SMX")
      (libsource (lib "eagle-import") (part "FM4007W-W"))
    )
    (comp (ref "C3")
      (value "100n")
      (footprint "eagle-import:C0402")
      (libsource (lib "eagle-import") (part "C-EUC0402"))
    )
    (comp (ref "J1")
      (value "6100XX11921_61000411921")
      (footprint "eagle-import:61000411921")
      (libsource (lib "eagle-import") (part "6100XX11921_61000411921"))
    )
    (comp (ref "Q7")
      (value "XTAL_CFPX-217")
      (footprint "eagle-import:FC-12M")
      (libsource (lib "eagle-import") (part "XTAL_CFPX-217"))
    )
    (comp (ref "R66")
      (value "0R")
      (footprint "eagle-import:R0402")
      (libsource (lib "eagle-import") (part "R-EU_R0402"))
    )
    (comp (ref "U$41")
      (value "LINX_BAT-HLD-001")
      (footprint "eagle-import:BATTERY_HOLDER_CR2032")
      (libsource (lib "eagle-import") (part "LINX_BAT-HLD-001"))
    )
    (comp (ref "U$42")
      (value "PCF8523")
      (footprint "eagle-import:SOIC-8")
      (libsource (lib "eagle-import") (part "PCF8523"))
    )
    (comp (ref "C1")
      (value "10n")
      (footprint "eagle-import:C0402")
      (libsource (lib "eagle-import") (part "C-EUC0402"))
    )
    (comp (ref "C6")
      (value "100n")
      (footprint "eagle-import:C0402")
      (libsource (lib "eagle-import") (part "C-EUC0402"))
    )
    (comp (ref "C14")
      (value "10u")
      (footprint "eagle-import:C0805")
      (libsource (lib "eagle-import") (part "rcl_334_C-EUC0805"))
    )
    (comp (ref "C41")
      (value "10n")
      (footprint "eagle-import:C0402")
      (libsource (lib "eagle-import") (part "C-EUC0402"))
    )
    (comp (ref "C63")
      (value "100n")
      (footprint "eagle-import:C0402")
      (libsource (lib "eagle-import") (part "C-EUC0402"))
    )
    (comp (ref "LED8")
      (value "GREEN")
      (footprint "eagle-import:SML0603")
      (libsource (lib "eagle-import") (part "LEDSML0603"))
    )
    (comp (ref "LED9")
      (value "RED")
      (footprint "eagle-import:SML0603")
      (libsource (lib "eagle-import") (part "LEDSML0603"))
    )
    (comp (ref "Q10")
      (value "BSS138")
      (footprint "eagle-import:SOT23")
      (libsource (lib "eagle-import") (part "MOSFET-NREFLOW"))
    )
    (comp (ref "R4")
      (value "0k")
      (footprint "eagle-import:R0402")
      (libsource (lib "eagle-import") (part "R-EU_R0402"))
    )
    (comp (ref "R5")
      (value "4k7")
      (footprint "eagle-import:R0402")
      (libsource (lib "eagle-import") (part "R-EU_R0402"))
    )
    (comp (ref "R6")
      (value "4k7")
      (footprint "eagle-import:R0402")
      (libsource (lib "eagle-import") (part "R-EU_R0402"))
    )
    (comp (ref "R30")
      (value "10k")
      (footprint "eagle-import:R0402")
      (libsource (lib "eagle-import") (part "R-EU_R0402"))
    )
    (comp (ref "R31")
      (value "10k")
      (footprint "eagle-import:R0402")
      (libsource (lib "eagle-import") (part "R-EU_R0402"))
    )
    (comp (ref "R32")
      (value "10k")
      (footprint "eagle-import:R0402")
      (libsource (lib "eagle-import") (part "R-EU_R0402"))
    )
    (comp (ref "R33")
      (value "10k")
      (footprint "eagle-import:R0402")
      (libsource (lib "eagle-import") (part "R-EU_R0402"))
    )
    (comp (ref "R34")
      (value "10k")
      (footprint "eagle-import:R0402")
      (libsource (lib "eagle-import") (part "R-EU_R0402"))
    )
    (comp (ref "R35")
      (value "560R")
      (footprint "eagle-import:R0402")
      (libsource (lib "eagle-import") (part "R-EU_R0402"))
    )
    (comp (ref "R36")
      (value "10k")
      (footprint "eagle-import:R0402")
      (libsource (lib "eagle-import") (part "R-EU_R0402"))
    )
    (comp (ref "R58")
      (value "56k")
      (footprint "eagle-import:R0402")
      (libsource (lib "eagle-import") (part "R-EU_R0402"))
    )
    (comp (ref "R60")
      (value "560R")
      (footprint "eagle-import:R0402")
      (libsource (lib "eagle-import") (part "R-EU_R0402"))
    )
    (comp (ref "R69")
      (value "10k")
      (footprint "eagle-import:R0402")
      (libsource (lib "eagle-import") (part "R-EU_R0402"))
    )
    (comp (ref "R70")
      (value "10k")
      (footprint "eagle-import:R0402")
      (libsource (lib "eagle-import") (part "R-EU_R0402"))
    )
    (comp (ref "R72")
      (value "4k7")
      (footprint "eagle-import:R0402")
      (libsource (lib "eagle-import") (part "R-EU_R0402"))
    )
    (comp (ref "R82")
      (value "10k")
      (footprint "eagle-import:R0402")
      (libsource (lib "eagle-import") (part "R-EU_R0402"))
    )
    (comp (ref "U$8")
      (value "NEXPERIA_PMV74EPER")
      (footprint "eagle-import:SOT23")
      (libsource (lib "eagle-import") (part "NEXPERIA_PMV74EPER"))
    )
    (comp (ref "U$12")
      (value "BOURNS_PEC12R-4225F-S0024")
      (footprint "eagle-import:BOURNS_PEC12RXXX")
      (libsource (lib "eagle-import") (part "BOURNS_PEC12R-4225F-S0024"))
    )
    (comp (ref "U$13")
      (value "FM4007W-W")
      (footprint "eagle-import:SMX")
      (libsource (lib "eagle-import") (part "FM4007W-W"))
    )
    (comp (ref "U$18")
      (value "JAE_DX07S016JA1R1500")
      (footprint "eagle-import:JAE_DX07S016JA1R1500")
      (libsource (lib "eagle-import") (part "JAE_DX07S016JA1R1500"))
    )
    (comp (ref "U$19")
      (value "FIDUCIAL")
      (footprint "eagle-import:FIDUCIAL_1MM")
      (libsource (lib "eagle-import") (part "FIDUCIAL"))
    )
    (comp (ref "U$21")
      (value "FIDUCIAL")
      (footprint "eagle-import:FIDUCIAL_1MM")
      (libsource (lib "eagle-import") (part "FIDUCIAL"))
    )
    (comp (ref "U$22")
      (value "BOURNS_ZV17K0603300NIR1HT")
      (footprint "eagle-import:0603")
      (libsource (lib "eagle-import") (part "BOURNS_ZV17K0603300NIR1HT"))
    )
    (comp (ref "U$23")
      (value "FIDUCIAL")
      (footprint "eagle-import:FIDUCIAL_1MM")
      (libsource (lib "eagle-import") (part "FIDUCIAL"))
    )
    (comp (ref "U$24")
      (value "FIDUCIAL")
      (footprint "eagle-import:FIDUCIAL_1MM")
      (libsource (lib "eagle-import") (part "FIDUCIAL"))
    )
    (comp (ref "U$26")
      (value "BOURNS_ZV17K0603300NIR1HT")
      (footprint "eagle-import:0603")
      (libsource (lib "eagle-import") (part "BOURNS_ZV17K0603300NIR1HT"))
    )
    (comp (ref "U$29")
      (value "KEYSTONE_FUSE_HOLDER_2PCS_5MMX20")
      (footprint "eagle-import:KEYSTONE_PC_5MM_FUSE_CLIP")
      (libsource (lib "eagle-import") (part "KEYSTONE_FUSE_HOLDER_2PCS_5MMX20"))
    )
    (comp (ref "U$30")
      (value "KEYSTONE_FUSE_HOLDER_2PCS_5MMX20")
      (footprint "eagle-import:KEYSTONE_PC_5MM_FUSE_CLIP")
      (libsource (lib "eagle-import") (part "KEYSTONE_FUSE_HOLDER_2PCS_5MMX20"))
    )
    (comp (ref "U$35")
      (value "WUERTH_PINHEADER_7POL_61001018221")
      (footprint "eagle-import:PINHEADER_SMD_7POL_ESP32_PRG")
      (libsource (lib "eagle-import") (part "WUERTH_PINHEADER_7POL_61001018221"))
    )
    (comp (ref "U$38")
      (value "PHOENIX_PTSA1.5/7-3.5-Z")
      (footprint "eagle-import:PHOENIX_PTSA_7POL_3.5MM")
      (libsource (lib "eagle-import") (part "PHOENIX_PTSA1.5/7-3.5-Z"))
    )
    (comp (ref "U$43")
      (value "OMRON_G6RL-14-ASI")
      (footprint "eagle-import:OMRON_G6RL-14-ASI")
      (libsource (lib "eagle-import") (part "OMRON_G6RL-14-ASI"))
    )
    (comp (ref "U1")
      (value "ESP32MOD")
      (footprint "eagle-import:ESP32MOD")
      (libsource (lib "eagle-import") (part "ESP32MOD"))
    )
  )
  (nets
    (net (code "1") (name "+3V3") (class "Default")
      (node (ref "C15") (pin "2") (pinfunction "2_2") (pintype "passive"))
      (node (ref "C21") (pin "2") (pinfunction "2_2") (pintype "passive"))
      (node (ref "J1") (pin "1") (pinfunction "1_1") (pintype "passive"))
      (node (ref "LED8") (pin "A") (pinfunction "A_A") (pintype "passive"))
      (node (ref "LED9") (pin "A") (pinfunction "A_A") (pintype "passive"))
      (node (ref "R18") (pin "2") (pinfunction "2_2") (pintype "passive"))
      (node (ref "U$13") (pin "KATHODE") (pinfunction "+VOUT_KATHODE") (pintype "passive"))
      (node (ref "U$20") (pin "12") (pinfunction "VDD_12") (pintype "power_in"))
      (node (ref "U$43") (pin "1") (pinfunction "A1_1") (pintype "input"))
      (node (ref "U$8") (pin "3") (pinfunction "D_3") (pintype "bidirectional"))
    )
    (net (code "2") (name "+3V3_PERMANENT") (class "Default")
      (node (ref "C12") (pin "1") (pinfunction "1_1") (pintype "passive"))
      (node (ref "C24") (pin "1") (pinfunction "1_1") (pintype "passive"))
      (node (ref "C3") (pin "2") (pinfunction "2_2") (pintype "passive"))
      (node (ref "R31") (pin "2") (pinfunction "2_2") (pintype "passive"))
      (node (ref "R32") (pin "2") (pinfunction "2_2") (pintype "passive"))
      (node (ref "R36") (pin "1") (pinfunction "1_1") (pintype "passive"))
      (node (ref "R4") (pin "2") (pinfunction "2_2") (pintype "passive"))
      (node (ref "R5") (pin "1") (pinfunction "1_1") (pintype "passive"))
      (node (ref "R55") (pin "1") (pinfunction "1_1") (pintype "passive"))
      (node (ref "R6") (pin "1") (pinfunction "1_1") (pintype "passive"))
      (node (ref "R72") (pin "1") (pinfunction "1_1") (pintype "passive"))
      (node (ref "U$36") (pin "VOUT1") (pinfunction "VOUT_VOUT1") (pintype "bidirectional"))
      (node (ref "U$36") (pin "VOUT2") (pinfunction "VOUT_VOUT2") (pintype "bidirectional"))
      (node (ref "U$36") (pin "VOUT3") (pinfunction "VOUT_VOUT3") (pintype "bidirectional"))
      (node (ref "U$42") (pin "8") (pinfunction "VCC_8") (pintype "power_in"))
      (node (ref "U$8") (pin "2") (pinfunction "S_2") (pintype "bidirectional"))
    )
    (net (code "3") (name "AAA") (class "Default")
      (node (ref "C1") (pin "2") (pinfunction "2_2") (pintype "passive"))
      (node (ref "C10") (pin "2") (pinfunction "2_2") (pintype "passive"))
      (node (ref "C11") (pin "2") (pinfunction "2_2") (pintype "passive"))
      (node (ref "C12") (pin "2") (pinfunction "2_2") (pintype "passive"))
      (node (ref "C13") (pin "2") (pinfunction "2_2") (pintype "passive"))
      (node (ref "C14") (pin "2") (pinfunction "2_2") (pintype "passive"))
      (node (ref "C15") (pin "1") (pinfunction "1_1") (pintype "passive"))
      (node (ref "C17") (pin "2") (pinfunction "2_2") (pintype "passive"))
      (node (ref "C19") (pin "2") (pinfunction "2_2") (pintype "passive"))
      (node (ref "C2") (pin "2") (pinfunction "2_2") (pintype "passive"))
      (node (ref "C21") (pin "1") (pinfunction "1_1") (pintype "passive"))
      (node (ref "C24") (pin "2") (pinfunction "2_2") (pintype "passive"))
      (node (ref "C3") (pin "1") (pinfunction "1_1") (pintype "passive"))
      (node (ref "C41") (pin "2") (pinfunction "2_2") (pintype "passive"))
      (node (ref "C6") (pin "2") (pinfunction "2_2") (pintype "passive"))
      (node (ref "C63") (pin "2") (pinfunction "2_2") (pintype "passive"))
      (node (ref "C7") (pin "2") (pinfunction "2_2") (pintype "passive"))
      (node (ref "C8") (pin "2") (pinfunction "2_2") (pintype "passive"))
      (node (ref "C9") (pin "2") (pinfunction "2_2") (pintype "passive"))
      (node (ref "J1") (pin "2") (pinfunction "2_2") (pintype "passive"))
      (node (ref "J3") (pin "1") (pinfunction "1_1") (pintype "passive"))
      (node (ref "LED1") (pin "C") (pinfunction "C_C") (pintype "passive"))
      (node (ref "LED13") (pin "C") (pinfunction "C_C") (pintype "passive"))
      (node (ref "LED15") (pin "C") (pinfunction "C_C") (pintype "passive"))
      (node (ref "LED16") (pin "C") (pinfunction "C_C") (pintype "passive"))
      (node (ref "LED2") (pin "C") (pinfunction "C_C") (pintype "passive"))
      (node (ref "LED3") (pin "C") (pinfunction "C_C") (pintype "passive"))
      (node (ref "LED4") (pin "C") (pinfunction "C_C") (pintype "passive"))
      (node (ref "LED5") (pin "C") (pinfunction "C_C") (pintype "passive"))
      (node (ref "LED6") (pin "C") (pinfunction "C_C") (pintype "passive"))
      (node (ref "Q10") (pin "2") (pinfunction "S_2") (pintype "bidirectional"))
      (node (ref "R10") (pin "1") (pinfunction "1_1") (pintype "passive"))
      (node (ref "R13") (pin "1") (pinfunction "1_1") (pintype "passive"))
      (node (ref "R16") (pin "1") (pinfunction "1_1") (pintype "passive"))
      (node (ref "R20") (pin "1") (pinfunction "1_1") (pintype "passive"))
      (node (ref "R22") (pin "1") (pinfunction "1_1") (pintype "passive"))
      (node (ref "R34") (pin "2") (pinfunction "2_2") (pintype "passive"))
      (node (ref "R38") (pin "2") (pinfunction "2_2") (pintype "passive"))
      (node (ref "R40") (pin "1") (pinfunction "1_1") (pintype "passive"))
      (node (ref "R43") (pin "1") (pinfunction "1_1") (pintype "passive"))
      (node (ref "R46") (pin "1") (pinfunction "1_1") (pintype "passive"))
      (node (ref "R50") (pin "1") (pinfunction "1_1") (pintype "passive"))
      (node (ref "R56") (pin "2") (pinfunction "2_2") (pintype "passive"))
      (node (ref "R57") (pin "2") (pinfunction "2_2") (pintype "passive"))
      (node (ref "R64") (pin "2") (pinfunction "2_2") (pintype "passive"))
      (node (ref "R68") (pin "2") (pinfunction "2_2") (pintype "passive"))
      (node (ref "R69") (pin "1") (pinfunction "1_1") (pintype "passive"))
      (node (ref "R70") (pin "2") (pinfunction "2_2") (pintype "passive"))
      (node (ref "U$1") (pin "2") (pinfunction "A2_2") (pintype "input"))
      (node (ref "U$12") (pin "2") (pinfunction "2_2") (pintype "passive"))
      (node (ref "U$12") (pin "C") (pinfunction "C_C") (pintype "output"))
      (node (ref "U$12") (pin "GND1") (pinfunction "GND_GND1") (pintype "passive"))
      (node (ref "U$12") (pin "GND2") (pinfunction "GND_GND2") (pintype "passive"))
      (node (ref "U$17") (pin "2") (pinfunction "A2_2") (pintype "input"))
      (node (ref "U$18") (pin "A1/B12") (pinfunction "GND_A1/B12") (pintype "bidirectional"))
      (node (ref "U$18") (pin "A12/B1") (pinfunction "GND_A12/B1") (pintype "bidirectional"))
      (node (ref "U$18") (pin "G1") (pinfunction "GND_G1") (pintype "bidirectional"))
      (node (ref "U$18") (pin "G2") (pinfunction "GND_G2") (pintype "bidirectional"))
      (node (ref "U$18") (pin "G3") (pinfunction "GND_G3") (pintype "bidirectional"))
      (node (ref "U$18") (pin "G4") (pinfunction "GND_G4") (pintype "bidirectional"))
      (node (ref "U$18") (pin "G5") (pinfunction "GND_G5") (pintype "bidirectional"))
      (node (ref "U$18") (pin "G6") (pinfunction "GND_G6") (pintype "bidirectional"))
      (node (ref "U$18") (pin "G7") (pinfunction "GND_G7") (pintype "bidirectional"))
      (node (ref "U$18") (pin "G8") (pinfunction "GND_G8") (pintype "bidirectional"))
      (node (ref "U$18") (pin "P1") (pinfunction "GND_P1") (pintype "bidirectional"))
      (node (ref "U$18") (pin "P2") (pinfunction "GND_P2") (pintype "bidirectional"))
      (node (ref "U$2") (pin "2") (pinfunction "A2_2") (pintype "input"))
      (node (ref "U$20") (pin "15") (pinfunction "DCDC_GND_15") (pintype "bidirectional"))
      (node (ref "U$20") (pin "9") (pinfunction "GND_9") (pintype "bidirectional"))
      (node (ref "U$3") (pin "2") (pinfunction "A2_2") (pintype "input"))
      (node (ref "U$35") (pin "7") (pinfunction "7_7") (pintype "passive"))
      (node (ref "U$36") (pin "GND") (pinfunction "GND_GND") (pintype "power_in"))
      (node (ref "U$36") (pin "PGND") (pinfunction "PGND_PGND") (pintype "power_in"))
      (node (ref "U$4") (pin "2") (pinfunction "A2_2") (pintype "input"))
      (node (ref "U$41") (pin "P$3") (pinfunction "GND_P$3") (pintype "passive"))
      (node (ref "U$42") (pin "4") (pinfunction "GND_4") (pintype "power_in"))
      (node (ref "U$5") (pin "2") (pinfunction "A2_2") (pintype "input"))
      (node (ref "U$6") (pin "2") (pinfunction "A2_2") (pintype "input"))
      (node (ref "U$7") (pin "2") (pinfunction "A2_2") (pintype "input"))
      (node (ref "U$9") (pin "2") (pinfunction "A2_2") (pintype "input"))
      (node (ref "U1") (pin "0") (pinfunction "GND_0") (pintype "power_in"))
      (node (ref "U1") (pin "1") (pinfunction "GND_1") (pintype "power_in"))
      (node (ref "U1") (pin "15") (pinfunction "GND_15") (pintype "power_in"))
      (node (ref "U1") (pin "38") (pinfunction "GND_38") (pintype "power_in"))
    )
    (net (code "4") (name "ADC_CLKIN") (class "Default")
      (node (ref "U$20") (pin "11") (pinfunction "CLKIN_11") (pintype "bidirectional"))
      (node (ref "U1") (pin "12") (pinfunction "IO27_12") (pintype "bidirectional"))
    )
    (net (code "5") (name "ADC_DIAG") (class "Default")
      (node (ref "R18") (pin "1") (pinfunction "1_1") (pintype "passive"))
      (node (ref "U$20") (pin "14") (pinfunction "DIAG_14") (pintype "bidirectional"))
    )
    (net (code "6") (name "ADC_DOUT") (class "Default")
      (node (ref "U$20") (pin "10") (pinfunction "DOUT_10") (pintype "bidirectional"))
      (node (ref "U1") (pin "13") (pinfunction "IO14_13") (pintype "bidirectional"))
    )
    (net (code "7") (name "CP") (class "Default")
      (node (ref "R27") (pin "2") (pinfunction "2_2") (pintype "passive"))
      (node (ref "U$17") (pin "4") (pinfunction "S1_4") (pintype "passive"))
      (node (ref "U$26") (pin "1") (pinfunction "1_1") (pintype "passive"))
      (node (ref "U$29") (pin "P$3") (pinfunction "2_P$3") (pintype "passive"))
      (node (ref "U$29") (pin "PAD2") (pinfunction "2_PAD2") (pintype "passive"))
      (node (ref "U$5") (pin "3") (pinfunction "Q1_3") (pintype "passive"))
    )
    (net (code "8") (name "CP_IN") (class "Default")
      (node (ref "U$29") (pin "P$1") (pinfunction "1_P$1") (pintype "passive"))
      (node (ref "U$29") (pin "PAD1") (pinfunction "1_PAD1") (pintype "passive"))
      (node (ref "U$38") (pin "2") (pinfunction "2_2") (pintype "bidirectional"))
    )
    (net (code "9") (name "EN") (class "Default")
      (node (ref "C63") (pin "1") (pinfunction "1_1") (pintype "passive"))
      (node (ref "R82") (pin "2") (pinfunction "2_2") (pintype "passive"))
      (node (ref "U$35") (pin "3") (pinfunction "3_3") (pintype "passive"))
      (node (ref "U1") (pin "3") (pinfunction "EN_3") (pintype "bidirectional"))
    )
    (net (code "10") (name "ESP32_VCC") (class "Default")
      (node (ref "C14") (pin "1") (pinfunction "1_1") (pintype "passive"))
      (node (ref "C6") (pin "1") (pinfunction "1_1") (pintype "passive"))
      (node (ref "R4") (pin "1") (pinfunction "1_1") (pintype "passive"))
      (node (ref "R82") (pin "1") (pinfunction "1_1") (pintype "passive"))
      (node (ref "U1") (pin "2") (pinfunction "VCC_2") (pintype "power_in"))
    )
    (net (code "11") (name "GPIO0") (class "Default")
      (node (ref "U$35") (pin "2") (pinfunction "2_2") (pintype "passive"))
      (node (ref "U1") (pin "25") (pinfunction "IO0_25") (pintype "bidirectional"))
    )
    (net (code "12") (name "GPIO_3V3_SWITCH") (class "Default")
      (node (ref "R36") (pin "2") (pinfunction "2_2") (pintype "passive"))
      (node (ref "U$8") (pin "1") (pinfunction "G_1") (pintype "bidirectional"))
      (node (ref "U1") (pin "14") (pinfunction "IO12_14") (pintype "bidirectional"))
    )
    (net (code "13") (name "GPIO_L1") (class "Default")
      (node (ref "R37") (pin "2") (pinfunction "2_2") (pintype "passive"))
      (node (ref "R38") (pin "1") (pinfunction "1_1") (pintype "passive"))
      (node (ref "U1") (pin "8") (pinfunction "IO32_8") (pintype "bidirectional"))
    )
    (net (code "14") (name "GPIO_L2") (class "Default")
      (node (ref "R63") (pin "2") (pinfunction "2_2") (pintype "passive"))
      (node (ref "R64") (pin "1") (pinfunction "1_1") (pintype "passive"))
      (node (ref "U1") (pin "10") (pinfunction "IO25_10") (pintype "bidirectional"))
    )
    (net (code "15") (name "GPIO_L3") (class "Default")
      (node (ref "R67") (pin "2") (pinfunction "2_2") (pintype "passive"))
      (node (ref "R68") (pin "1") (pinfunction "1_1") (pintype "passive"))
      (node (ref "U1") (pin "11") (pinfunction "IO26_11") (pintype "bidirectional"))
    )
    (net (code "16") (name "GPIO_PE_BREAKER") (class "Default")
      (node (ref "Q10") (pin "1") (pinfunction "G_1") (pintype "bidirectional"))
      (node (ref "R34") (pin "1") (pinfunction "1_1") (pintype "passive"))
      (node (ref "R60") (pin "1") (pinfunction "1_1") (pintype "passive"))
      (node (ref "U1") (pin "30") (pinfunction "IO18_30") (pintype "bidirectional"))
    )
    (net (code "17") (name "GPIO_PP1") (class "Default")
      (node (ref "R1") (pin "2") (pinfunction "2_2") (pintype "passive"))
      (node (ref "R39") (pin "1") (pinfunction "1_1") (pintype "passive"))
      (node (ref "R40") (pin "2") (pinfunction "2_2") (pintype "passive"))
      (node (ref "U1") (pin "29") (pinfunction "IO5_29") (pintype "bidirectional"))
    )
    (net (code "18") (name "GPIO_PP2") (class "Default")
      (node (ref "R10") (pin "2") (pinfunction "2_2") (pintype "passive"))
      (node (ref "R11") (pin "2") (pinfunction "2_2") (pintype "passive"))
      (node (ref "R9") (pin "1") (pinfunction "1_1") (pintype "passive"))
      (node (ref "U1") (pin "26") (pinfunction "IO4_26") (pintype "bidirectional"))
    )
    (net (code "19") (name "GPIO_PP3") (class "Default")
      (node (ref "R12") (pin "1") (pinfunction "1_1") (pintype "passive"))
      (node (ref "R13") (pin "2") (pinfunction "2_2") (pintype "passive"))
      (node (ref "R14") (pin "2") (pinfunction "2_2") (pintype "passive"))
      (node (ref "U1") (pin "27") (pinfunction "IO16_27") (pintype "bidirectional"))
    )
    (net (code "20") (name "GPIO_PP4") (class "Default")
      (node (ref "R15") (pin "1") (pinfunction "1_1") (pintype "passive"))
      (node (ref "R16") (pin "2") (pinfunction "2_2") (pintype "passive"))
      (node (ref "R41") (pin "2") (pinfunction "2_2") (pintype "passive"))
      (node (ref "U1") (pin "28") (pinfunction "IO17_28") (pintype "bidirectional"))
    )
    (net (code "21") (name "GPIO_PP5") (class "Default")
      (node (ref "R42") (pin "1") (pinfunction "1_1") (pintype "passive"))
      (node (ref "R43") (pin "2") (pinfunction "2_2") (pintype "passive"))
      (node (ref "R44") (pin "2") (pinfunction "2_2") (pintype "passive"))
    )
    (net (code "22") (name "GPIO_ROTARY_A") (class "Default")
      (node (ref "C41") (pin "1") (pinfunction "1_1") (pintype "passive"))
      (node (ref "R30") (pin "1") (pinfunction "1_1") (pintype "passive"))
      (node (ref "U$12") (pin "B") (pinfunction "B_B") (pintype "output"))
      (node (ref "U1") (pin "5") (pinfunction "SENSOR_VN_5") (pintype "bidirectional"))
    )
    (net (code "23") (name "GPIO_ROTARY_B") (class "Default")
      (node (ref "C1") (pin "1") (pinfunction "1_1") (pintype "passive"))
      (node (ref "R33") (pin "1") (pinfunction "1_1") (pintype "passive"))
      (node (ref "U$12") (pin "A") (pinfunction "A_A") (pintype "output"))
      (node (ref "U1") (pin "7") (pinfunction "IO35_7") (pintype "bidirectional"))
    )
    (net (code "24") (name "GPIO_ROTARY_BUTTON") (class "Default")
      (node (ref "R72") (pin "2") (pinfunction "2_2") (pintype "passive"))
      (node (ref "U$12") (pin "1") (pinfunction "1_1") (pintype "passive"))
      (node (ref "U1") (pin "4") (pinfunction "SENSOR_VP_4") (pintype "bidirectional"))
    )
    (net (code "25") (name "GPIO_RTC") (class "Default")
      (node (ref "R66") (pin "2") (pinfunction "2_2") (pintype "passive"))
    )
    (net (code "26") (name "GPIO_STATE_AB") (class "Default")
      (node (ref "R19") (pin "1") (pinfunction "1_1") (pintype "passive"))
      (node (ref "R20") (pin "2") (pinfunction "2_2") (pintype "passive"))
      (node (ref "R48") (pin "2") (pinfunction "2_2") (pintype "passive"))
      (node (ref "U1") (pin "31") (pinfunction "IO19_31") (pintype "bidirectional"))
    )
    (net (code "27") (name "GPIO_STATE_C") (class "Default")
      (node (ref "R21") (pin "1") (pinfunction "1_1") (pintype "passive"))
      (node (ref "R22") (pin "2") (pinfunction "2_2") (pintype "passive"))
      (node (ref "R23") (pin "2") (pinfunction "2_2") (pintype "passive"))
      (node (ref "U1") (pin "33") (pinfunction "IO21_33") (pintype "bidirectional"))
    )
    (net (code "28") (name "GPIO_STATE_D_FAULT") (class "Default")
      (node (ref "R49") (pin "1") (pinfunction "1_1") (pintype "passive"))
      (node (ref "R50") (pin "2") (pinfunction "2_2") (pintype "passive"))
      (node (ref "R51") (pin "2") (pinfunction "2_2") (pintype "passive"))
      (node (ref "U1") (pin "36") (pinfunction "IO22_36") (pintype "bidirectional"))
    )
    (net (code "29") (name "GPIO_STATE_E") (class "Default")
      (node (ref "R45") (pin "1") (pinfunction "1_1") (pintype "passive"))
      (node (ref "R46") (pin "2") (pinfunction "2_2") (pintype "passive"))
      (node (ref "R47") (pin "2") (pinfunction "2_2") (pintype "passive"))
      (node (ref "U1") (pin "37") (pinfunction "IO23_37") (pintype "bidirectional"))
    )
    (net (code "30") (name "L1") (class "Default")
      (node (ref "U$27") (pin "1") (pinfunction "1_1") (pintype "bidirectional"))
      (node (ref "U$38") (pin "7") (pinfunction "7_7") (pintype "bidirectional"))
    )
    (net (code "31") (name "L2") (class "Default")
      (node (ref "U$10") (pin "1") (pinfunction "1_1") (pintype "bidirectional"))
      (node (ref "U$38") (pin "6") (pinfunction "6_6") (pintype "bidirectional"))
    )
    (net (code "32") (name "L3") (class "Default")
      (node (ref "U$16") (pin "1") (pinfunction "1_1") (pintype "bidirectional"))
      (node (ref "U$38") (pin "5") (pinfunction "5_5") (pintype "bidirectional"))
    )
    (net (code "33") (name "N") (class "Default")
      (node (ref "U$10") (pin "4") (pinfunction "4_4") (pintype "bidirectional"))
      (node (ref "U$16") (pin "4") (pinfunction "4_4") (pintype "bidirectional"))
      (node (ref "U$27") (pin "4") (pinfunction "4_4") (pintype "bidirectional"))
      (node (ref "U$38") (pin "4") (pinfunction "4_4") (pintype "bidirectional"))
    )
    (net (code "34") (name "Net-(J3-Pad2)") (class "Default")
      (node (ref "J3") (pin "2") (pinfunction "2_2") (pintype "passive"))
      (node (ref "J3") (pin "5") (pinfunction "5_5") (pintype "passive"))
    )
    (net (code "35") (name "Net-(L2-Pad1)") (class "Default")
      (node (ref "L2") (pin "1") (pinfunction "1_1") (pintype "passive"))
      (node (ref "U$36") (pin "L1") (pinfunction "L1_L1") (pintype "output"))
    )
    (net (code "36") (name "Net-(L2-Pad2)") (class "Default")
      (node (ref "L2") (pin "2") (pinfunction "2_2") (pintype "passive"))
      (node (ref "U$36") (pin "L2") (pinfunction "L2_L2") (pintype "output"))
    )
    (net (code "37") (name "Net-(LED1-PadA)") (class "Default")
      (node (ref "LED1") (pin "A") (pinfunction "A_A") (pintype "passive"))
      (node (ref "R11") (pin "1") (pinfunction "1_1") (pintype "passive"))
    )
    (net (code "38") (name "Net-(LED2-PadA)") (class "Default")
      (node (ref "LED2") (pin "A") (pinfunction "A_A") (pintype "passive"))
      (node (ref "R14") (pin "1") (pinfunction "1_1") (pintype "passive"))
    )
    (net (code "39") (name "Net-(LED3-PadA)") (class "Default")
      (node (ref "LED3") (pin "A") (pinfunction "A_A") (pintype "passive"))
      (node (ref "R41") (pin "1") (pinfunction "1_1") (pintype "passive"))
    )
    (net (code "40") (name "Net-(LED4-PadA)") (class "Default")
      (node (ref "LED4") (pin "A") (pinfunction "A_A") (pintype "passive"))
      (node (ref "R44") (pin "1") (pinfunction "1_1") (pintype "passive"))
    )
    (net (code "41") (name "Net-(LED5-PadA)") (class "Default")
      (node (ref "LED5") (pin "A") (pinfunction "A_A") (pintype "passive"))
      (node (ref "R48") (pin "1") (pinfunction "1_1") (pintype "passive"))
    )
    (net (code "42") (name "Net-(LED6-PadA)") (class "Default")
      (node (ref "LED6") (pin "A") (pinfunction "A_A") (pintype "passive"))
      (node (ref "R23") (pin "1") (pinfunction "1_1") (pintype "passive"))
    )
    (net (code "43") (name "Net-(LED8-PadC)") (class "Default")
      (node (ref "LED8") (pin "C") (pinfunction "C_C") (pintype "passive"))
      (node (ref "R60") (pin "2") (pinfunction "2_2") (pintype "passive"))
    )
    (net (code "44") (name "Net-(LED9-PadC)") (class "Default")
      (node (ref "LED9") (pin "C") (pinfunction "C_C") (pintype "passive"))
      (node (ref "R35") (pin "2") (pinfunction "2_2") (pintype "passive"))
    )
    (net (code "45") (name "Net-(LED13-PadA)") (class "Default")
      (node (ref "LED13") (pin "A") (pinfunction "A_A") (pintype "passive"))
      (node (ref "R47") (pin "1") (pinfunction "1_1") (pintype "passive"))
    )
    (net (code "46") (name "Net-(LED15-PadA)") (class "Default")
      (node (ref "LED15") (pin "A") (pinfunction "A_A") (pintype "passive"))
      (node (ref "R1") (pin "1") (pinfunction "1_1") (pintype "passive"))
    )
    (net (code "47") (name "Net-(LED16-PadA)") (class "Default")
      (node (ref "LED16") (pin "A") (pinfunction "A_A") (pintype "passive"))
      (node (ref "R51") (pin "1") (pinfunction "1_1") (pintype "passive"))
    )
    (net (code "48") (name "Net-(Q10-D)") (class "Default")
      (node (ref "Q10") (pin "3") (pinfunction "D_3") (pintype "bidirectional"))
      (node (ref "R35") (pin "1") (pinfunction "1_1") (pintype "passive"))
      (node (ref "U$13") (pin "ANODE") (pinfunction "+VIN_ANODE") (pintype "passive"))
      (node (ref "U$43") (pin "5") (pinfunction "A2_5") (pintype "input"))
    )
    (net (code "49") (name "Net-(R30-Pad2)") (class "Default")
      (node (ref "R30") (pin "2") (pinfunction "2_2") (pintype "passive"))
      (node (ref "R31") (pin "1") (pinfunction "1_1") (pintype "passive"))
    )
    (net (code "50") (name "Net-(R32-Pad1)") (class "Default")
      (node (ref "R32") (pin "1") (pinfunction "1_1") (pintype "passive"))
      (node (ref "R33") (pin "2") (pinfunction "2_2") (pintype "passive"))
    )
    (net (code "51") (name "Net-(R55-Pad2)") (class "Default")
      (node (ref "R55") (pin "2") (pinfunction "2_2") (pintype "passive"))
      (node (ref "R56") (pin "1") (pinfunction "1_1") (pintype "passive"))
      (node (ref "U$36") (pin "FB") (pinfunction "FB_FB") (pintype "bidirectional"))
    )
    (net (code "52") (name "Net-(R57-Pad1)") (class "Default")
      (node (ref "R57") (pin "1") (pinfunction "1_1") (pintype "passive"))
      (node (ref "U$36") (pin "PFM/PWM") (pinfunction "PFM/PWM_PFM/PWM") (pintype "output"))
    )
    (net (code "53") (name "Net-(R59-Pad1)") (class "Default")
      (node (ref "R59") (pin "1") (pinfunction "1_1") (pintype "passive"))
      (node (ref "U$36") (pin "EN") (pinfunction "EN_EN") (pintype "input"))
    )
    (net (code "54") (name "Net-(U$1-A1)") (class "Default")
      (node (ref "R9") (pin "2") (pinfunction "2_2") (pintype "passive"))
      (node (ref "U$1") (pin "1") (pinfunction "A1_1") (pintype "input"))
    )
    (net (code "55") (name "Net-(U$2-A1)") (class "Default")
      (node (ref "R12") (pin "2") (pinfunction "2_2") (pintype "passive"))
      (node (ref "U$2") (pin "1") (pinfunction "A1_1") (pintype "input"))
    )
    (net (code "56") (name "Net-(U$3-A1)") (class "Default")
      (node (ref "R15") (pin "2") (pinfunction "2_2") (pintype "passive"))
      (node (ref "U$3") (pin "1") (pinfunction "A1_1") (pintype "input"))
    )
    (net (code "57") (name "Net-(U$4-A1)") (class "Default")
      (node (ref "R42") (pin "2") (pinfunction "2_2") (pintype "passive"))
      (node (ref "U$4") (pin "1") (pinfunction "A1_1") (pintype "input"))
    )
    (net (code "58") (name "Net-(U$5-A1)") (class "Default")
      (node (ref "R19") (pin "2") (pinfunction "2_2") (pintype "passive"))
      (node (ref "U$5") (pin "1") (pinfunction "A1_1") (pintype "input"))
    )
    (net (code "59") (name "Net-(U$6-A1)") (class "Default")
      (node (ref "R49") (pin "2") (pinfunction "2_2") (pintype "passive"))
      (node (ref "U$6") (pin "1") (pinfunction "A1_1") (pintype "input"))
    )
    (net (code "60") (name "Net-(U$7-A1)") (class "Default")
      (node (ref "R21") (pin "2") (pinfunction "2_2") (pintype "passive"))
      (node (ref "U$7") (pin "1") (pinfunction "A1_1") (pintype "input"))
    )
    (net (code "61") (name "Net-(U$7-S1)") (class "Default")
      (node (ref "R17") (pin "1") (pinfunction "1_1") (pintype "passive"))
      (node (ref "U$7") (pin "4") (pinfunction "S1_4") (pintype "passive"))
    )
    (net (code "62") (name "Net-(U$9-A1)") (class "Default")
      (node (ref "R39") (pin "2") (pinfunction "2_2") (pintype "passive"))
      (node (ref "U$9") (pin "1") (pinfunction "A1_1") (pintype "input"))
    )
    (net (code "63") (name "Net-(U$10-Pad2)") (class "Default")
      (node (ref "U$10") (pin "2") (pinfunction "2_2") (pintype "bidirectional"))
      (node (ref "U$10") (pin "3") (pinfunction "3_3") (pintype "bidirectional"))
    )
    (net (code "64") (name "Net-(U$10-Pad6)") (class "Default")
      (node (ref "U$10") (pin "6") (pinfunction "6_6") (pintype "bidirectional"))
      (node (ref "U$14") (pin "1") (pinfunction "1_1") (pintype "passive"))
    )
    (net (code "65") (name "Net-(U$11-+VIN)") (class "Default")
      (node (ref "U$11") (pin "ANODE") (pinfunction "+VIN_ANODE") (pintype "passive"))
      (node (ref "U$5") (pin "4") (pinfunction "S1_4") (pintype "passive"))
      (node (ref "U$6") (pin "3") (pinfunction "Q1_3") (pintype "passive"))
    )
    (net (code "66") (name "Net-(U$11-+VOUT)") (class "Default")
      (node (ref "R26") (pin "1") (pinfunction "1_1") (pintype "passive"))
      (node (ref "U$11") (pin "KATHODE") (pinfunction "+VOUT_KATHODE") (pintype "passive"))
      (node (ref "U$6") (pin "4") (pinfunction "S1_4") (pintype "passive"))
      (node (ref "U$7") (pin "3") (pinfunction "Q1_3") (pintype "passive"))
    )
    (net (code "67") (name "Net-(U$15-+VIN)") (class "Default")
      (node (ref "U$10") (pin "5") (pinfunction "5_5") (pintype "bidirectional"))
      (node (ref "U$14") (pin "2") (pinfunction "2_2") (pintype "passive"))
      (node (ref "U$15") (pin "ANODE") (pinfunction "+VIN_ANODE") (pintype "passive"))
    )
    (net (code "68") (name "Net-(U$15-+VOUT)") (class "Default")
      (node (ref "C2") (pin "1") (pinfunction "1_1") (pintype "passive"))
      (node (ref "C9") (pin "1") (pinfunction "1_1") (pintype "passive"))
      (node (ref "R63") (pin "1") (pinfunction "1_1") (pintype "passive"))
      (node (ref "U$15") (pin "KATHODE") (pinfunction "+VOUT_KATHODE") (pintype "passive"))
    )
    (net (code "69") (name "Net-(U$16-Pad2)") (class "Default")
      (node (ref "U$16") (pin "2") (pinfunction "2_2") (pintype "bidirectional"))
      (node (ref "U$16") (pin "3") (pinfunction "3_3") (pintype "bidirectional"))
    )
    (net (code "70") (name "Net-(U$16-Pad6)") (class "Default")
      (node (ref "U$16") (pin "6") (pinfunction "6_6") (pintype "bidirectional"))
      (node (ref "U$32") (pin "1") (pinfunction "1_1") (pintype "passive"))
    )
    (net (code "71") (name "Net-(U$17-A1)") (class "Default")
      (node (ref "R45") (pin "2") (pinfunction "2_2") (pintype "passive"))
      (node (ref "U$17") (pin "1") (pinfunction "A1_1") (pintype "input"))
    )
    (net (code "72") (name "Net-(U$18-CC2)") (class "Default")
      (node (ref "R69") (pin "2") (pinfunction "2_2") (pintype "passive"))
      (node (ref "U$18") (pin "B5") (pinfunction "CC2_B5") (pintype "bidirectional"))
    )
    (net (code "73") (name "Net-(U$20-DCDC_HGND)") (class "Default")
      (node (ref "C16") (pin "1") (pinfunction "1_1") (pintype "passive"))
      (node (ref "C18") (pin "1") (pinfunction "1_1") (pintype "passive"))
      (node (ref "C20") (pin "1") (pinfunction "1_1") (pintype "passive"))
      (node (ref "C22") (pin "2") (pinfunction "2_2") (pintype "passive"))
      (node (ref "C23") (pin "2") (pinfunction "2_2") (pintype "passive"))
      (node (ref "R24") (pin "1") (pinfunction "1_1") (pintype "passive"))
      (node (ref "R28") (pin "2") (pinfunction "2_2") (pintype "passive"))
      (node (ref "R29") (pin "2") (pinfunction "2_2") (pintype "passive"))
      (node (ref "U$20") (pin "2") (pinfunction "DCDC_HGND_2") (pintype "bidirectional"))
      (node (ref "U$20") (pin "8") (pinfunction "HGND_8") (pintype "power_in"))
      (node (ref "U$34") (pin "2") (pinfunction "+VOUT_2") (pintype "passive"))
    )
    (net (code "74") (name "Net-(U$20-DCDC_IN)") (class "Default")
      (node (ref "C17") (pin "1") (pinfunction "1_1") (pintype "passive"))
      (node (ref "U$20") (pin "13") (pinfunction "LDO_OUT_13") (pintype "bidirectional"))
      (node (ref "U$20") (pin "16") (pinfunction "DCDC_IN_16") (pintype "bidirectional"))
    )
    (net (code "75") (name "Net-(U$20-DCDC_OUT)") (class "Default")
      (node (ref "C20") (pin "2") (pinfunction "2_2") (pintype "passive"))
      (node (ref "C22") (pin "1") (pinfunction "1_1") (pintype "passive"))
      (node (ref "C23") (pin "1") (pinfunction "1_1") (pintype "passive"))
      (node (ref "U$20") (pin "1") (pinfunction "DCDC_OUT_1") (pintype "bidirectional"))
      (node (ref "U$20") (pin "3") (pinfunction "HLDO_IN_3") (pintype "bidirectional"))
    )
    (net (code "76") (name "Net-(U$20-HLDO_OUT)") (class "Default")
      (node (ref "C16") (pin "2") (pinfunction "2_2") (pintype "passive"))
      (node (ref "C18") (pin "2") (pinfunction "2_2") (pintype "passive"))
      (node (ref "U$20") (pin "5") (pinfunction "HLDO_OUT_5") (pintype "bidirectional"))
    )
    (net (code "77") (name "Net-(U$20-INN)") (class "Default")
      (node (ref "C25") (pin "2") (pinfunction "2_2") (pintype "passive"))
      (node (ref "R29") (pin "1") (pinfunction "1_1") (pintype "passive"))
      (node (ref "U$20") (pin "7") (pinfunction "INN_7") (pintype "bidirectional"))
    )
    (net (code "78") (name "Net-(U$20-INP)") (class "Default")
      (node (ref "C25") (pin "1") (pinfunction "1_1") (pintype "passive"))
      (node (ref "R25") (pin "1") (pinfunction "1_1") (pintype "passive"))
      (node (ref "U$20") (pin "6") (pinfunction "INP_6") (pintype "bidirectional"))
    )
    (net (code "79") (name "Net-(U$27-Pad2)") (class "Default")
      (node (ref "U$27") (pin "2") (pinfunction "2_2") (pintype "bidirectional"))
      (node (ref "U$27") (pin "3") (pinfunction "3_3") (pintype "bidirectional"))
    )
    (net (code "80") (name "Net-(U$27-Pad6)") (class "Default")
      (node (ref "U$27") (pin "6") (pinfunction "6_6") (pintype "bidirectional"))
      (node (ref "U$28") (pin "1") (pinfunction "1_1") (pintype "passive"))
    )
    (net (code "81") (name "Net-(U$31-+VIN)") (class "Default")
      (node (ref "U$27") (pin "5") (pinfunction "5_5") (pintype "bidirectional"))
      (node (ref "U$28") (pin "2") (pinfunction "2_2") (pintype "passive"))
      (node (ref "U$31") (pin "ANODE") (pinfunction "+VIN_ANODE") (pintype "passive"))
    )
    (net (code "82") (name "Net-(U$31-+VOUT)") (class "Default")
      (node (ref "C7") (pin "1") (pinfunction "1_1") (pintype "passive"))
      (node (ref "C8") (pin "1") (pinfunction "1_1") (pintype "passive"))
      (node (ref "R37") (pin "1") (pinfunction "1_1") (pintype "passive"))
      (node (ref "U$31") (pin "KATHODE") (pinfunction "+VOUT_KATHODE") (pintype "passive"))
    )
    (net (code "83") (name "Net-(U$33-+VIN)") (class "Default")
      (node (ref "U$16") (pin "5") (pinfunction "5_5") (pintype "bidirectional"))
      (node (ref "U$32") (pin "2") (pinfunction "2_2") (pintype "passive"))
      (node (ref "U$33") (pin "ANODE") (pinfunction "+VIN_ANODE") (pintype "passive"))
    )
    (net (code "84") (name "Net-(U$33-+VOUT)") (class "Default")
      (node (ref "C11") (pin "1") (pinfunction "1_1") (pintype "passive"))
      (node (ref "C13") (pin "1") (pinfunction "1_1") (pintype "passive"))
      (node (ref "R67") (pin "1") (pinfunction "1_1") (pintype "passive"))
      (node (ref "U$33") (pin "KATHODE") (pinfunction "+VOUT_KATHODE") (pintype "passive"))
    )
    (net (code "85") (name "Net-(U$34-+VIN)") (class "Default")
      (node (ref "R24") (pin "2") (pinfunction "2_2") (pintype "passive"))
      (node (ref "R25") (pin "2") (pinfunction "2_2") (pintype "passive"))
      (node (ref "R27") (pin "1") (pinfunction "1_1") (pintype "passive"))
      (node (ref "U$34") (pin "1") (pinfunction "+VIN_1") (pintype "passive"))
    )
    (net (code "86") (name "Net-(U$42-OSCI)") (class "Default")
      (node (ref "Q7") (pin "2") (pinfunction "2_2") (pintype "passive"))
      (node (ref "U$42") (pin "1") (pinfunction "OSCI_1") (pintype "bidirectional"))
    )
    (net (code "87") (name "Net-(U$42-OSCO)") (class "Default")
      (node (ref "Q7") (pin "1") (pinfunction "1_1") (pintype "passive"))
      (node (ref "U$42") (pin "2") (pinfunction "OSCO_2") (pintype "bidirectional"))
    )
    (net (code "88") (name "Net-(U$42-VBAT)") (class "Default")
      (node (ref "U$41") (pin "P$1") (pinfunction "VCC_P$1") (pintype "power_in"))
      (node (ref "U$41") (pin "P$2") (pinfunction "VCC_P$2") (pintype "power_in"))
      (node (ref "U$42") (pin "3") (pinfunction "VBAT_3") (pintype "bidirectional"))
    )
    (net (code "89") (name "Net-(U$42-{slash}INT)") (class "Default")
      (node (ref "R66") (pin "1") (pinfunction "1_1") (pintype "passive"))
      (node (ref "U$42") (pin "7") (pinfunction "/INT_7") (pintype "bidirectional"))
    )
    (net (code "90") (name "PE") (class "Default")
      (node (ref "R17") (pin "2") (pinfunction "2_2") (pintype "passive"))
      (node (ref "R26") (pin "2") (pinfunction "2_2") (pintype "passive"))
      (node (ref "R28") (pin "1") (pinfunction "1_1") (pintype "passive"))
      (node (ref "U$1") (pin "4") (pinfunction "S1_4") (pintype "passive"))
      (node (ref "U$17") (pin "3") (pinfunction "Q1_3") (pintype "passive"))
      (node (ref "U$2") (pin "4") (pinfunction "S1_4") (pintype "passive"))
      (node (ref "U$22") (pin "2") (pinfunction "2_2") (pintype "passive"))
      (node (ref "U$26") (pin "2") (pinfunction "2_2") (pintype "passive"))
      (node (ref "U$3") (pin "4") (pinfunction "S1_4") (pintype "passive"))
      (node (ref "U$4") (pin "4") (pinfunction "S1_4") (pintype "passive"))
      (node (ref "U$43") (pin "2") (pinfunction "P1_2") (pintype "passive"))
      (node (ref "U$9") (pin "4") (pinfunction "S1_4") (pintype "passive"))
    )
    (net (code "91") (name "PE_IN") (class "Default")
      (node (ref "U$38") (pin "3") (pinfunction "3_3") (pintype "bidirectional"))
      (node (ref "U$43") (pin "4") (pinfunction "S1_4") (pintype "passive"))
    )
    (net (code "92") (name "PP") (class "Default")
      (node (ref "R2") (pin "2") (pinfunction "2_2") (pintype "passive"))
      (node (ref "R3") (pin "2") (pinfunction "2_2") (pintype "passive"))
      (node (ref "R7") (pin "2") (pinfunction "2_2") (pintype "passive"))
      (node (ref "R73") (pin "2") (pinfunction "2_2") (pintype "passive"))
      (node (ref "R8") (pin "2") (pinfunction "2_2") (pintype "passive"))
      (node (ref "U$22") (pin "1") (pinfunction "1_1") (pintype "passive"))
      (node (ref "U$30") (pin "P$3") (pinfunction "2_P$3") (pintype "passive"))
      (node (ref "U$30") (pin "PAD2") (pinfunction "2_PAD2") (pintype "passive"))
    )
    (net (code "93") (name "PP1") (class "Default")
      (node (ref "R8") (pin "1") (pinfunction "1_1") (pintype "passive"))
      (node (ref "U$9") (pin "3") (pinfunction "Q1_3") (pintype "passive"))
    )
    (net (code "94") (name "PP2") (class "Default")
      (node (ref "R3") (pin "1") (pinfunction "1_1") (pintype "passive"))
      (node (ref "U$1") (pin "3") (pinfunction "Q1_3") (pintype "passive"))
    )
    (net (code "95") (name "PP3") (class "Default")
      (node (ref "R73") (pin "1") (pinfunction "1_1") (pintype "passive"))
      (node (ref "U$2") (pin "3") (pinfunction "Q1_3") (pintype "passive"))
    )
    (net (code "96") (name "PP4") (class "Default")
      (node (ref "R2") (pin "1") (pinfunction "1_1") (pintype "passive"))
      (node (ref "U$3") (pin "3") (pinfunction "Q1_3") (pintype "passive"))
    )
    (net (code "97") (name "PP5") (class "Default")
      (node (ref "R7") (pin "1") (pinfunction "1_1") (pintype "passive"))
      (node (ref "U$4") (pin "3") (pinfunction "Q1_3") (pintype "passive"))
    )
    (net (code "98") (name "PP_IN") (class "Default")
      (node (ref "U$30") (pin "P$1") (pinfunction "1_P$1") (pintype "passive"))
      (node (ref "U$30") (pin "PAD1") (pinfunction "1_PAD1") (pintype "passive"))
      (node (ref "U$38") (pin "1") (pinfunction "1_1") (pintype "bidirectional"))
    )
    (net (code "99") (name "RXD") (class "Default")
      (node (ref "U$35") (pin "1") (pinfunction "1_1") (pintype "passive"))
      (node (ref "U1") (pin "34") (pinfunction "RXD0_34") (pintype "bidirectional"))
    )
    (net (code "100") (name "SCL") (class "Default")
      (node (ref "J1") (pin "3") (pinfunction "3_3") (pintype "passive"))
      (node (ref "J3") (pin "3") (pinfunction "3_3") (pintype "passive"))
      (node (ref "R5") (pin "2") (pinfunction "2_2") (pintype "passive"))
      (node (ref "U$42") (pin "6") (pinfunction "SCL_6") (pintype "bidirectional"))
      (node (ref "U1") (pin "9") (pinfunction "IO33_9") (pintype "bidirectional"))
    )
    (net (code "101") (name "SDA") (class "Default")
      (node (ref "J1") (pin "4") (pinfunction "4_4") (pintype "passive"))
      (node (ref "J3") (pin "4") (pinfunction "4_4") (pintype "passive"))
      (node (ref "R6") (pin "2") (pinfunction "2_2") (pintype "passive"))
      (node (ref "U$42") (pin "5") (pinfunction "SDA_5") (pintype "bidirectional"))
      (node (ref "U1") (pin "6") (pinfunction "IO34_6") (pintype "bidirectional"))
    )
    (net (code "102") (name "SYSTEM_LOAD") (class "Default")
      (node (ref "C10") (pin "1") (pinfunction "1_1") (pintype "passive"))
      (node (ref "C19") (pin "1") (pinfunction "1_1") (pintype "passive"))
      (node (ref "J3") (pin "6") (pinfunction "6_6") (pintype "passive"))
      (node (ref "R59") (pin "2") (pinfunction "2_2") (pintype "passive"))
      (node (ref "U$36") (pin "VIN1") (pinfunction "VIN_VIN1") (pintype "input"))
      (node (ref "U$36") (pin "VIN2") (pinfunction "VIN_VIN2") (pintype "input"))
      (node (ref "U$36") (pin "VIN3") (pinfunction "VIN_VIN3") (pintype "input"))
      (node (ref "U$36") (pin "VINA") (pinfunction "VINA_VINA") (pintype "input"))
    )
    (net (code "103") (name "TXD") (class "Default")
      (node (ref "U$35") (pin "5") (pinfunction "5_5") (pintype "passive"))
      (node (ref "U1") (pin "35") (pinfunction "TXD0_35") (pintype "bidirectional"))
    )
    (net (code "104") (name "USB_5V") (class "Default")
      (node (ref "R58") (pin "1") (pinfunction "1_1") (pintype "passive"))
      (node (ref "R70") (pin "1") (pinfunction "1_1") (pintype "passive"))
      (node (ref "U$18") (pin "A4/B9") (pinfunction "VBUS_A4/B9") (pintype "bidirectional"))
      (node (ref "U$18") (pin "B4/A9") (pinfunction "VBUS_B4/A9") (pintype "bidirectional"))
    )
    (net (code "105") (name "USB_CC") (class "Default")
      (node (ref "R58") (pin "2") (pinfunction "2_2") (pintype "passive"))
      (node (ref "U$18") (pin "A5") (pinfunction "CC1_A5") (pintype "bidirectional"))
    )
    (net (code "106") (name "USB_D+") (class "Default")
      (node (ref "U$18") (pin "A6") (pinfunction "A6_D+1_A6") (pintype "bidirectional"))
    )
    (net (code "107") (name "USB_D-") (class "Default")
      (node (ref "U$18") (pin "A7") (pinfunction "A7_D-_A7") (pintype "bidirectional"))
    )
    (net (code "108") (name "unconnected-(U$10-Pad7)") (class "Default")
      (node (ref "U$10") (pin "7") (pinfunction "7_7") (pintype "bidirectional"))
    )
    (net (code "109") (name "unconnected-(U$10-Pad8)") (class "Default")
      (node (ref "U$10") (pin "8") (pinfunction "8_8") (pintype "bidirectional"))
    )
    (net (code "110") (name "unconnected-(U$16-Pad7)") (class "Default")
      (node (ref "U$16") (pin "7") (pinfunction "7_7") (pintype "bidirectional"))
    )
    (net (code "111") (name "unconnected-(U$16-Pad8)") (class "Default")
      (node (ref "U$16") (pin "8") (pinfunction "8_8") (pintype "bidirectional"))
    )
    (net (code "112") (name "unconnected-(U$18-B6_D+-PadB6)") (class "Default")
      (node (ref "U$18") (pin "B6") (pinfunction "B6_D+_B6") (pintype "bidirectional"))
    )
    (net (code "113") (name "unconnected-(U$18-B7_D--PadB7)") (class "Default")
      (node (ref "U$18") (pin "B7") (pinfunction "B7_D-_B7") (pintype "bidirectional"))
    )
    (net (code "114") (name "unconnected-(U$18-SBU1-PadA8)") (class "Default")
      (node (ref "U$18") (pin "A8") (pinfunction "SBU1_A8") (pintype "bidirectional"))
    )
    (net (code "115") (name "unconnected-(U$18-SBU2-PadB8)") (class "Default")
      (node (ref "U$18") (pin "B8") (pinfunction "SBU2_B8") (pintype "bidirectional"))
    )
    (net (code "116") (name "unconnected-(U$27-Pad7)") (class "Default")
      (node (ref "U$27") (pin "7") (pinfunction "7_7") (pintype "bidirectional"))
    )
    (net (code "117") (name "unconnected-(U$27-Pad8)") (class "Default")
      (node (ref "U$27") (pin "8") (pinfunction "8_8") (pintype "bidirectional"))
    )
    (net (code "118") (name "unconnected-(U$43-Q1-Pad3)") (class "Default")
      (node (ref "U$43") (pin "3") (pinfunction "Q1_3") (pintype "passive"))
    )
    (net (code "119") (name "unconnected-(U1-IO2-Pad24)") (class "Default")
      (node (ref "U1") (pin "24") (pinfunction "IO2_24") (pintype "bidirectional"))
    )
    (net (code "120") (name "unconnected-(U1-IO13-Pad16)") (class "Default")
      (node (ref "U1") (pin "16") (pinfunction "IO13_16") (pintype "bidirectional"))
    )
    (net (code "121") (name "unconnected-(U1-IO15-Pad23)") (class "Default")
      (node (ref "U1") (pin "23") (pinfunction "IO15_23") (pintype "bidirectional"))
    )
  )
)
